# Out_current_sensor_UVW.net
KiCad netlist of a schematic drawn in Altium Designer
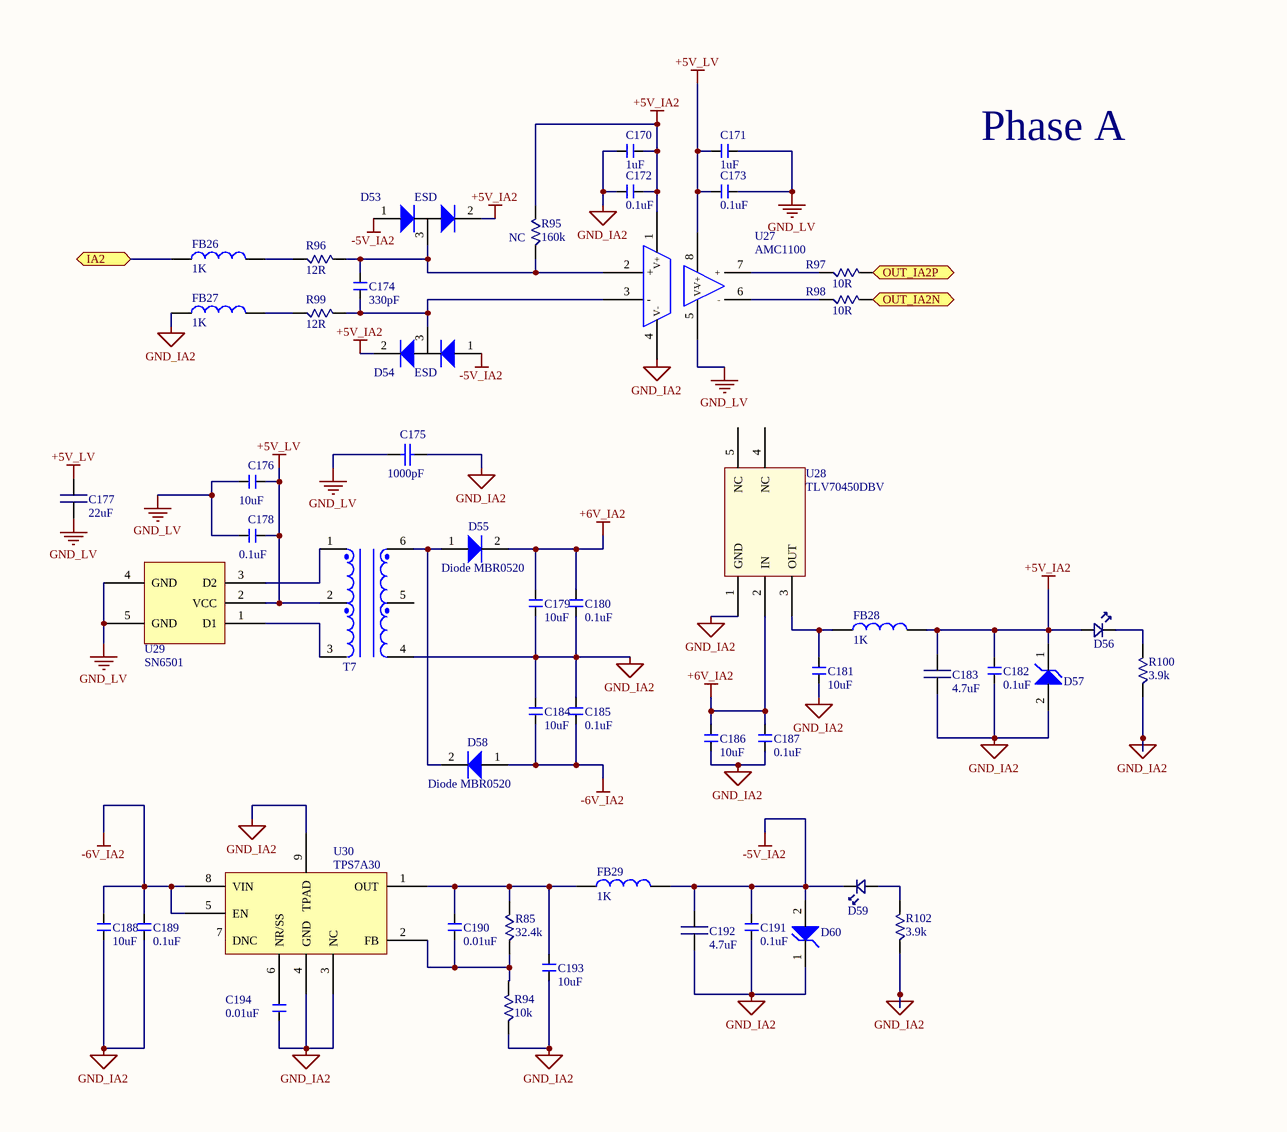
[diagram p0: Out_current_sensor_UVW.SchDoc, top left]
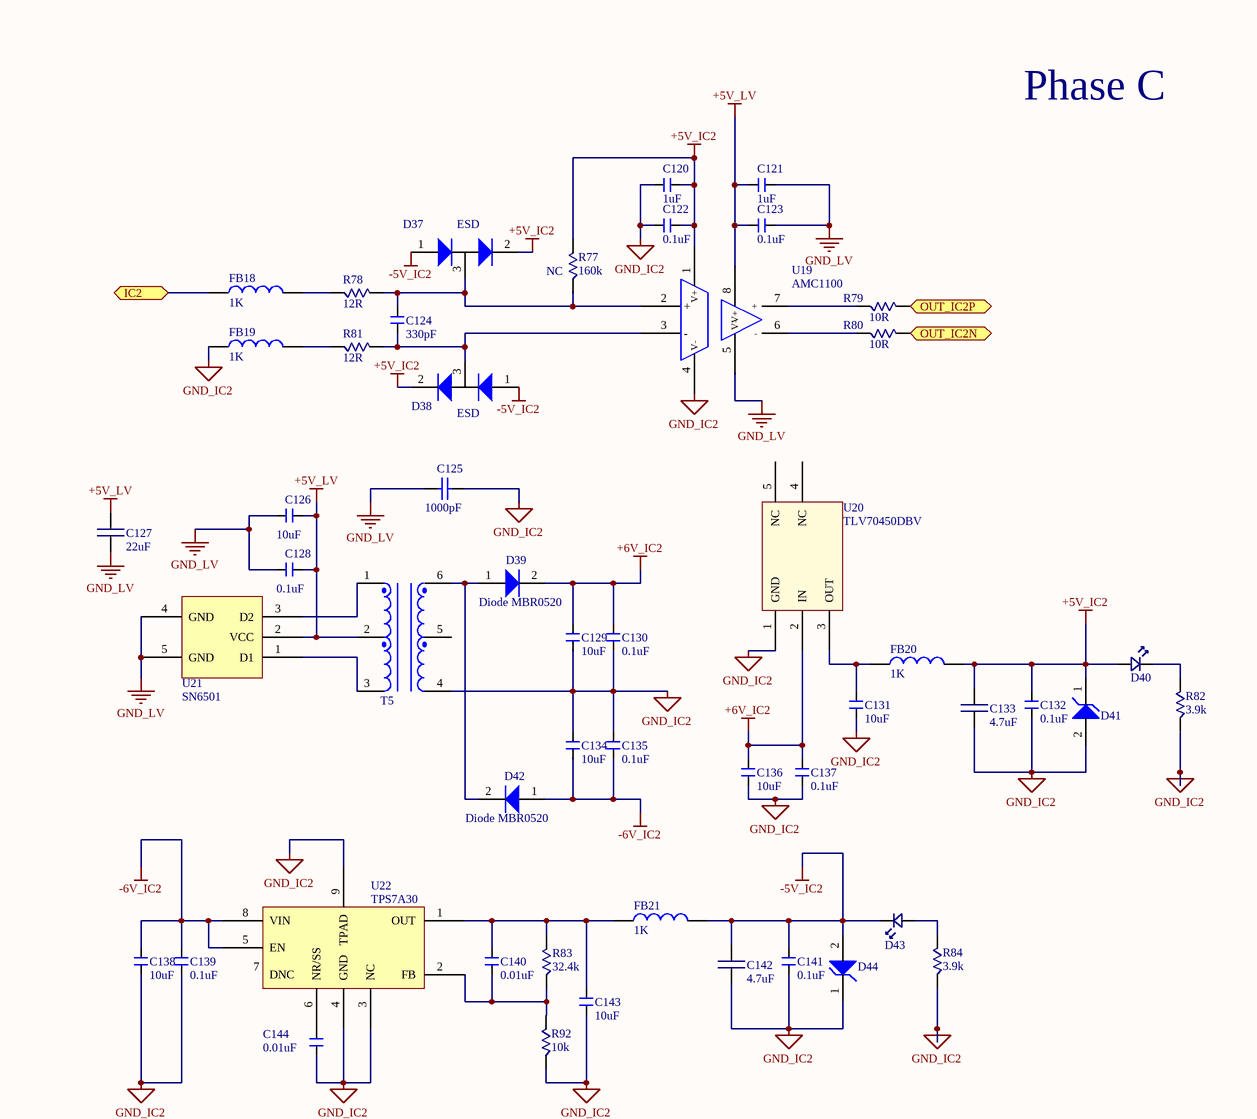
[diagram p1: Out_current_sensor_UVW.SchDoc, top right]
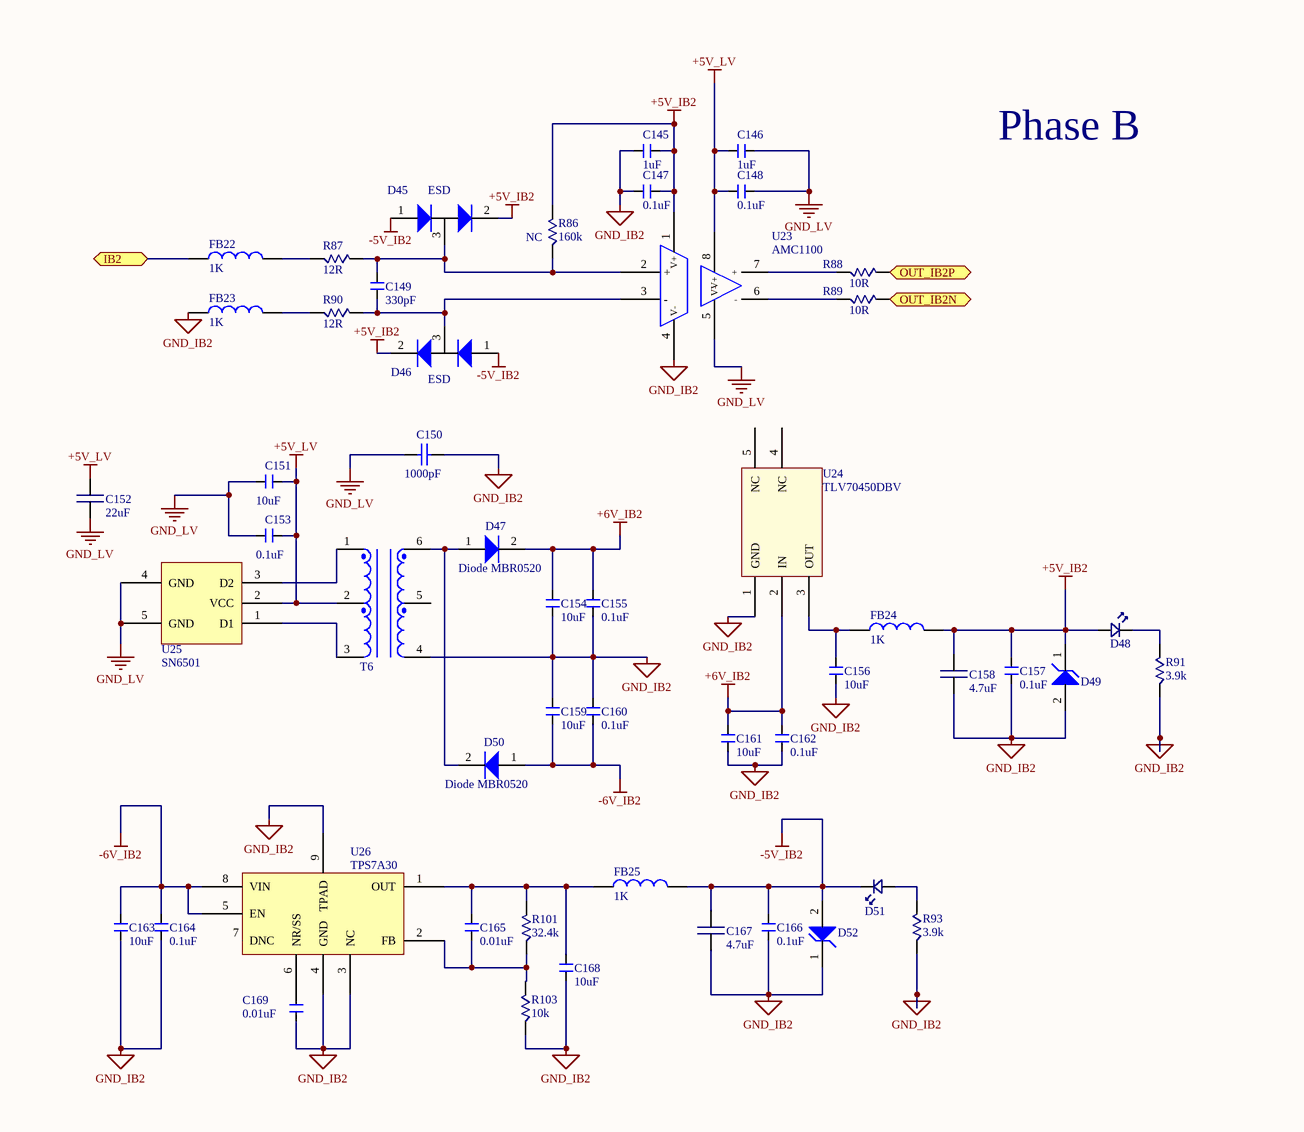
[diagram p2: Out_current_sensor_UVW.SchDoc, bottom left]

(export (version "E")
  (design (tool "Eeschema 10.0.6"))
  (components
    (comp (ref "C120")
      (value "1uF")
      (footprint "0603 (1608 Metric)")
      (description "CAP CER 1UF 50V X5R 0603")
      (fields (field (name "PART") "1276-1860-1-ND") (field (name "Comment") "Cap 0603_new"))
      (libsource (lib "Library_Microgrid") (part "Cap 0603_new"))
    )
    (comp (ref "C121")
      (value "1uF")
      (footprint "0603 (1608 Metric)")
      (description "CAP CER 1UF 50V X5R 0603")
      (fields (field (name "PART") "1276-1860-1-ND") (field (name "Comment") "Cap 0603_new"))
      (libsource (lib "Library_Microgrid") (part "Cap 0603_new"))
    )
    (comp (ref "C122")
      (value "0.1uF")
      (footprint "0603 (1608 Metric)")
      (description "CAP CER 0.1UF 50V Y5V 0603")
      (fields (field (name "PART") "311-1343-6-ND") (field (name "Comment") "Cap 0603_new"))
      (libsource (lib "Library_Microgrid") (part "Cap 0603_new"))
    )
    (comp (ref "C123")
      (value "0.1uF")
      (footprint "0603 (1608 Metric)")
      (description "CAP CER 0.1UF 50V Y5V 0603")
      (fields (field (name "PART") "311-1343-6-ND") (field (name "Comment") "Cap 0603_new"))
      (libsource (lib "Library_Microgrid") (part "Cap 0603_new"))
    )
    (comp (ref "C124")
      (value "330pF")
      (footprint "0603 (1608 Metric)")
      (description "CAP CER 330PF 50V C0G 0603")
      (fields (field (name "PART") "445-7033-2-ND") (field (name "Comment") "Cap 0603_new"))
      (libsource (lib "Library_Microgrid") (part "Cap 0603_new"))
    )
    (comp (ref "C125")
      (value "1000pF")
      (footprint "RAD-0.3")
      (description "CAP CER 1000PF 1KV Y5P RADIAL")
      (fields
        (field (name "PART") "1251PH-ND")
        (field (name "Comment") "Cap TH")
        (field (name "PUBLISHER") "Altium Limited")
      )
      (libsource (lib "Miscellaneous Devices") (part "Cap"))
    )
    (comp (ref "C126")
      (value "10uF")
      (footprint "0603 (1608 Metric)")
      (description "CAP CER 10UF 35V X5R 0805")
      (fields (field (name "PART") "490-10515-1-ND") (field (name "Comment") "Cap 0603_new"))
      (libsource (lib "Library_Microgrid") (part "Cap 0603_new"))
    )
    (comp (ref "C127")
      (value "22uF")
      (footprint "0805 (2012 metric)")
      (description "CAP CER 22UF 35V X5R 0805")
      (fields (field (name "PART") "445-14428-1-ND") (field (name "Comment") "Cap 0805"))
      (libsource (lib "Library_Microgrid") (part "Cap 0805"))
    )
    (comp (ref "C128")
      (value "0.1uF")
      (footprint "0603 (1608 Metric)")
      (description "CAP CER 0.1UF 50V Y5V 0603")
      (fields (field (name "PART") "311-1343-6-ND") (field (name "Comment") "Cap 0603_new"))
      (libsource (lib "Library_Microgrid") (part "Cap 0603_new"))
    )
    (comp (ref "C129")
      (value "10uF")
      (footprint "0603 (1608 Metric)")
      (description "CAP CER 10UF 35V X5R 0805")
      (fields (field (name "PART") "490-10515-1-ND") (field (name "Comment") "Cap 0603_new"))
      (libsource (lib "Library_Microgrid") (part "Cap 0603_new"))
    )
    (comp (ref "C130")
      (value "0.1uF")
      (footprint "0603 (1608 Metric)")
      (description "CAP CER 0.1UF 50V Y5V 0603")
      (fields (field (name "PART") "311-1343-6-ND") (field (name "Comment") "Cap 0603_new"))
      (libsource (lib "Library_Microgrid") (part "Cap 0603_new"))
    )
    (comp (ref "C131")
      (value "10uF")
      (footprint "0603 (1608 Metric)")
      (description "CAP CER 10UF 35V X5R 0805")
      (fields (field (name "PART") "490-10515-1-ND") (field (name "Comment") "Cap 0603_new"))
      (libsource (lib "Library_Microgrid") (part "Cap 0603_new"))
    )
    (comp (ref "C132")
      (value "0.1uF")
      (footprint "0603 (1608 Metric)")
      (description "CAP CER 0.1UF 50V Y5V 0603")
      (fields (field (name "PART") "311-1343-6-ND") (field (name "Comment") "Cap 0603_new"))
      (libsource (lib "Library_Microgrid") (part "Cap 0603_new"))
    )
    (comp (ref "C133")
      (value "4.7uF")
      (footprint "0805 (2012 metric)")
      (description "CAP CER 4.7UF 50V X5R 0805")
      (fields (field (name "PART") "445-5980-1-ND") (field (name "Comment") "Cap 0805"))
      (libsource (lib "Library_Microgrid") (part "Cap 0805"))
    )
    (comp (ref "C134")
      (value "10uF")
      (footprint "0603 (1608 Metric)")
      (description "CAP CER 10UF 35V X5R 0805")
      (fields (field (name "PART") "490-10515-1-ND") (field (name "Comment") "Cap 0603_new"))
      (libsource (lib "Library_Microgrid") (part "Cap 0603_new"))
    )
    (comp (ref "C135")
      (value "0.1uF")
      (footprint "0603 (1608 Metric)")
      (description "CAP CER 0.1UF 50V Y5V 0603")
      (fields (field (name "PART") "311-1343-6-ND") (field (name "Comment") "Cap 0603_new"))
      (libsource (lib "Library_Microgrid") (part "Cap 0603_new"))
    )
    (comp (ref "C136")
      (value "10uF")
      (footprint "0603 (1608 Metric)")
      (description "CAP CER 10UF 35V X5R 0805")
      (fields (field (name "PART") "490-10515-1-ND") (field (name "Comment") "Cap 0603_new"))
      (libsource (lib "Library_Microgrid") (part "Cap 0603_new"))
    )
    (comp (ref "C137")
      (value "0.1uF")
      (footprint "0603 (1608 Metric)")
      (description "CAP CER 0.1UF 50V Y5V 0603")
      (fields (field (name "PART") "311-1343-6-ND") (field (name "Comment") "Cap 0603_new"))
      (libsource (lib "Library_Microgrid") (part "Cap 0603_new"))
    )
    (comp (ref "C138")
      (value "10uF")
      (footprint "0603 (1608 Metric)")
      (description "CAP CER 10UF 35V X5R 0805")
      (fields (field (name "PART") "490-10515-1-ND") (field (name "Comment") "Cap 0603_new"))
      (libsource (lib "Library_Microgrid") (part "Cap 0603_new"))
    )
    (comp (ref "C139")
      (value "0.1uF")
      (footprint "0603 (1608 Metric)")
      (description "CAP CER 0.1UF 50V Y5V 0603")
      (fields (field (name "PART") "311-1343-6-ND") (field (name "Comment") "Cap 0603_new"))
      (libsource (lib "Library_Microgrid") (part "Cap 0603_new"))
    )
    (comp (ref "C140")
      (value "0.01uF")
      (footprint "0603 (1608 Metric)")
      (description "CAP CER 10000PF 100V X7R 0603")
      (fields (field (name "PART") "478-7418-1-ND") (field (name "Comment") "Cap 0603_new"))
      (libsource (lib "Library_Microgrid") (part "Cap 0603_new"))
    )
    (comp (ref "C141")
      (value "0.1uF")
      (footprint "0603 (1608 Metric)")
      (description "CAP CER 0.1UF 50V Y5V 0603")
      (fields (field (name "PART") "311-1343-6-ND") (field (name "Comment") "Cap 0603_new"))
      (libsource (lib "Library_Microgrid") (part "Cap 0603_new"))
    )
    (comp (ref "C142")
      (value "4.7uF")
      (footprint "0805 (2012 metric)")
      (description "CAP CER 4.7UF 50V X5R 0805")
      (fields (field (name "PART") "445-5980-1-ND") (field (name "Comment") "Cap 0805"))
      (libsource (lib "Library_Microgrid") (part "Cap 0805"))
    )
    (comp (ref "C143")
      (value "10uF")
      (footprint "0603 (1608 Metric)")
      (description "CAP CER 10UF 35V X5R 0805")
      (fields (field (name "PART") "490-10515-1-ND") (field (name "Comment") "Cap 0603_new"))
      (libsource (lib "Library_Microgrid") (part "Cap 0603_new"))
    )
    (comp (ref "C144")
      (value "0.01uF")
      (footprint "0603 (1608 Metric)")
      (description "CAP CER 10000PF 100V X7R 0603")
      (fields (field (name "PART") "478-7418-1-ND") (field (name "Comment") "Cap 0603_new"))
      (libsource (lib "Library_Microgrid") (part "Cap 0603_new"))
    )
    (comp (ref "C145")
      (value "1uF")
      (footprint "0603 (1608 Metric)")
      (description "CAP CER 1UF 50V X5R 0603")
      (fields (field (name "PART") "1276-1860-1-ND") (field (name "Comment") "Cap 0603_new"))
      (libsource (lib "Library_Microgrid") (part "Cap 0603_new"))
    )
    (comp (ref "C146")
      (value "1uF")
      (footprint "0603 (1608 Metric)")
      (description "CAP CER 1UF 50V X5R 0603")
      (fields (field (name "PART") "1276-1860-1-ND") (field (name "Comment") "Cap 0603_new"))
      (libsource (lib "Library_Microgrid") (part "Cap 0603_new"))
    )
    (comp (ref "C147")
      (value "0.1uF")
      (footprint "0603 (1608 Metric)")
      (description "CAP CER 0.1UF 50V Y5V 0603")
      (fields (field (name "PART") "311-1343-6-ND") (field (name "Comment") "Cap 0603_new"))
      (libsource (lib "Library_Microgrid") (part "Cap 0603_new"))
    )
    (comp (ref "C148")
      (value "0.1uF")
      (footprint "0603 (1608 Metric)")
      (description "CAP CER 0.1UF 50V Y5V 0603")
      (fields (field (name "PART") "311-1343-6-ND") (field (name "Comment") "Cap 0603_new"))
      (libsource (lib "Library_Microgrid") (part "Cap 0603_new"))
    )
    (comp (ref "C149")
      (value "330pF")
      (footprint "0603 (1608 Metric)")
      (description "CAP CER 330PF 50V C0G 0603")
      (fields (field (name "PART") "445-7033-2-ND") (field (name "Comment") "Cap 0603_new"))
      (libsource (lib "Library_Microgrid") (part "Cap 0603_new"))
    )
    (comp (ref "C150")
      (value "1000pF")
      (footprint "RAD-0.3")
      (description "CAP CER 1000PF 1KV Y5P RADIAL")
      (fields
        (field (name "PART") "1251PH-ND")
        (field (name "Comment") "Cap TH")
        (field (name "PUBLISHER") "Altium Limited")
      )
      (libsource (lib "Miscellaneous Devices") (part "Cap"))
    )
    (comp (ref "C151")
      (value "10uF")
      (footprint "0603 (1608 Metric)")
      (description "CAP CER 10UF 35V X5R 0805")
      (fields (field (name "PART") "490-10515-1-ND") (field (name "Comment") "Cap 0603_new"))
      (libsource (lib "Library_Microgrid") (part "Cap 0603_new"))
    )
    (comp (ref "C152")
      (value "22uF")
      (footprint "0805 (2012 metric)")
      (description "CAP CER 22UF 35V X5R 0805")
      (fields (field (name "PART") "445-14428-1-ND") (field (name "Comment") "Cap 0805"))
      (libsource (lib "Library_Microgrid") (part "Cap 0805"))
    )
    (comp (ref "C153")
      (value "0.1uF")
      (footprint "0603 (1608 Metric)")
      (description "CAP CER 0.1UF 50V Y5V 0603")
      (fields (field (name "PART") "311-1343-6-ND") (field (name "Comment") "Cap 0603_new"))
      (libsource (lib "Library_Microgrid") (part "Cap 0603_new"))
    )
    (comp (ref "C154")
      (value "10uF")
      (footprint "0603 (1608 Metric)")
      (description "CAP CER 10UF 35V X5R 0805")
      (fields (field (name "PART") "490-10515-1-ND") (field (name "Comment") "Cap 0603_new"))
      (libsource (lib "Library_Microgrid") (part "Cap 0603_new"))
    )
    (comp (ref "C155")
      (value "0.1uF")
      (footprint "0603 (1608 Metric)")
      (description "CAP CER 0.1UF 50V Y5V 0603")
      (fields (field (name "PART") "311-1343-6-ND") (field (name "Comment") "Cap 0603_new"))
      (libsource (lib "Library_Microgrid") (part "Cap 0603_new"))
    )
    (comp (ref "C156")
      (value "10uF")
      (footprint "0603 (1608 Metric)")
      (description "CAP CER 10UF 35V X5R 0805")
      (fields (field (name "PART") "490-10515-1-ND") (field (name "Comment") "Cap 0603_new"))
      (libsource (lib "Library_Microgrid") (part "Cap 0603_new"))
    )
    (comp (ref "C157")
      (value "0.1uF")
      (footprint "0603 (1608 Metric)")
      (description "CAP CER 0.1UF 50V Y5V 0603")
      (fields (field (name "PART") "311-1343-6-ND") (field (name "Comment") "Cap 0603_new"))
      (libsource (lib "Library_Microgrid") (part "Cap 0603_new"))
    )
    (comp (ref "C158")
      (value "4.7uF")
      (footprint "0805 (2012 metric)")
      (description "CAP CER 4.7UF 50V X5R 0805")
      (fields (field (name "PART") "445-5980-1-ND") (field (name "Comment") "Cap 0805"))
      (libsource (lib "Library_Microgrid") (part "Cap 0805"))
    )
    (comp (ref "C159")
      (value "10uF")
      (footprint "0603 (1608 Metric)")
      (description "CAP CER 10UF 35V X5R 0805")
      (fields (field (name "PART") "490-10515-1-ND") (field (name "Comment") "Cap 0603_new"))
      (libsource (lib "Library_Microgrid") (part "Cap 0603_new"))
    )
    (comp (ref "C160")
      (value "0.1uF")
      (footprint "0603 (1608 Metric)")
      (description "CAP CER 0.1UF 50V Y5V 0603")
      (fields (field (name "PART") "311-1343-6-ND") (field (name "Comment") "Cap 0603_new"))
      (libsource (lib "Library_Microgrid") (part "Cap 0603_new"))
    )
    (comp (ref "C161")
      (value "10uF")
      (footprint "0603 (1608 Metric)")
      (description "CAP CER 10UF 35V X5R 0805")
      (fields (field (name "PART") "490-10515-1-ND") (field (name "Comment") "Cap 0603_new"))
      (libsource (lib "Library_Microgrid") (part "Cap 0603_new"))
    )
    (comp (ref "C162")
      (value "0.1uF")
      (footprint "0603 (1608 Metric)")
      (description "CAP CER 0.1UF 50V Y5V 0603")
      (fields (field (name "PART") "311-1343-6-ND") (field (name "Comment") "Cap 0603_new"))
      (libsource (lib "Library_Microgrid") (part "Cap 0603_new"))
    )
    (comp (ref "C163")
      (value "10uF")
      (footprint "0603 (1608 Metric)")
      (description "CAP CER 10UF 35V X5R 0805")
      (fields (field (name "PART") "490-10515-1-ND") (field (name "Comment") "Cap 0603_new"))
      (libsource (lib "Library_Microgrid") (part "Cap 0603_new"))
    )
    (comp (ref "C164")
      (value "0.1uF")
      (footprint "0603 (1608 Metric)")
      (description "CAP CER 0.1UF 50V Y5V 0603")
      (fields (field (name "PART") "311-1343-6-ND") (field (name "Comment") "Cap 0603_new"))
      (libsource (lib "Library_Microgrid") (part "Cap 0603_new"))
    )
    (comp (ref "C165")
      (value "0.01uF")
      (footprint "0603 (1608 Metric)")
      (description "CAP CER 10000PF 100V X7R 0603")
      (fields (field (name "PART") "478-7418-1-ND") (field (name "Comment") "Cap 0603_new"))
      (libsource (lib "Library_Microgrid") (part "Cap 0603_new"))
    )
    (comp (ref "C166")
      (value "0.1uF")
      (footprint "0603 (1608 Metric)")
      (description "CAP CER 0.1UF 50V Y5V 0603")
      (fields (field (name "PART") "311-1343-6-ND") (field (name "Comment") "Cap 0603_new"))
      (libsource (lib "Library_Microgrid") (part "Cap 0603_new"))
    )
    (comp (ref "C167")
      (value "4.7uF")
      (footprint "0805 (2012 metric)")
      (description "CAP CER 4.7UF 50V X5R 0805")
      (fields (field (name "PART") "445-5980-1-ND") (field (name "Comment") "Cap 0805"))
      (libsource (lib "Library_Microgrid") (part "Cap 0805"))
    )
    (comp (ref "C168")
      (value "10uF")
      (footprint "0603 (1608 Metric)")
      (description "CAP CER 10UF 35V X5R 0805")
      (fields (field (name "PART") "490-10515-1-ND") (field (name "Comment") "Cap 0603_new"))
      (libsource (lib "Library_Microgrid") (part "Cap 0603_new"))
    )
    (comp (ref "C169")
      (value "0.01uF")
      (footprint "0603 (1608 Metric)")
      (description "CAP CER 10000PF 100V X7R 0603")
      (fields (field (name "PART") "478-7418-1-ND") (field (name "Comment") "Cap 0603_new"))
      (libsource (lib "Library_Microgrid") (part "Cap 0603_new"))
    )
    (comp (ref "C170")
      (value "1uF")
      (footprint "0603 (1608 Metric)")
      (description "CAP CER 1UF 50V X5R 0603")
      (fields (field (name "PART") "1276-1860-1-ND") (field (name "Comment") "Cap 0603_new"))
      (libsource (lib "Library_Microgrid") (part "Cap 0603_new"))
    )
    (comp (ref "C171")
      (value "1uF")
      (footprint "0603 (1608 Metric)")
      (description "CAP CER 1UF 50V X5R 0603")
      (fields (field (name "PART") "1276-1860-1-ND") (field (name "Comment") "Cap 0603_new"))
      (libsource (lib "Library_Microgrid") (part "Cap 0603_new"))
    )
    (comp (ref "C172")
      (value "0.1uF")
      (footprint "0603 (1608 Metric)")
      (description "CAP CER 0.1UF 50V Y5V 0603")
      (fields (field (name "PART") "311-1343-6-ND") (field (name "Comment") "Cap 0603_new"))
      (libsource (lib "Library_Microgrid") (part "Cap 0603_new"))
    )
    (comp (ref "C173")
      (value "0.1uF")
      (footprint "0603 (1608 Metric)")
      (description "CAP CER 0.1UF 50V Y5V 0603")
      (fields (field (name "PART") "311-1343-6-ND") (field (name "Comment") "Cap 0603_new"))
      (libsource (lib "Library_Microgrid") (part "Cap 0603_new"))
    )
    (comp (ref "C174")
      (value "330pF")
      (footprint "0603 (1608 Metric)")
      (description "CAP CER 330PF 50V C0G 0603")
      (fields (field (name "PART") "445-7033-2-ND") (field (name "Comment") "Cap 0603_new"))
      (libsource (lib "Library_Microgrid") (part "Cap 0603_new"))
    )
    (comp (ref "C175")
      (value "1000pF")
      (footprint "RAD-0.3")
      (description "CAP CER 1000PF 1KV Y5P RADIAL")
      (fields
        (field (name "PART") "1251PH-ND")
        (field (name "Comment") "Cap TH")
        (field (name "PUBLISHER") "Altium Limited")
      )
      (libsource (lib "Miscellaneous Devices") (part "Cap"))
    )
    (comp (ref "C176")
      (value "10uF")
      (footprint "0603 (1608 Metric)")
      (description "CAP CER 10UF 35V X5R 0805")
      (fields (field (name "PART") "490-10515-1-ND") (field (name "Comment") "Cap 0603_new"))
      (libsource (lib "Library_Microgrid") (part "Cap 0603_new"))
    )
    (comp (ref "C177")
      (value "22uF")
      (footprint "0805 (2012 metric)")
      (description "CAP CER 22UF 35V X5R 0805")
      (fields (field (name "PART") "445-14428-1-ND") (field (name "Comment") "Cap 0805"))
      (libsource (lib "Library_Microgrid") (part "Cap 0805"))
    )
    (comp (ref "C178")
      (value "0.1uF")
      (footprint "0603 (1608 Metric)")
      (description "CAP CER 0.1UF 50V Y5V 0603")
      (fields (field (name "PART") "311-1343-6-ND") (field (name "Comment") "Cap 0603_new"))
      (libsource (lib "Library_Microgrid") (part "Cap 0603_new"))
    )
    (comp (ref "C179")
      (value "10uF")
      (footprint "0603 (1608 Metric)")
      (description "CAP CER 10UF 35V X5R 0805")
      (fields (field (name "PART") "490-10515-1-ND") (field (name "Comment") "Cap 0603_new"))
      (libsource (lib "Library_Microgrid") (part "Cap 0603_new"))
    )
    (comp (ref "C180")
      (value "0.1uF")
      (footprint "0603 (1608 Metric)")
      (description "CAP CER 0.1UF 50V Y5V 0603")
      (fields (field (name "PART") "311-1343-6-ND") (field (name "Comment") "Cap 0603_new"))
      (libsource (lib "Library_Microgrid") (part "Cap 0603_new"))
    )
    (comp (ref "C181")
      (value "10uF")
      (footprint "0603 (1608 Metric)")
      (description "CAP CER 10UF 35V X5R 0805")
      (fields (field (name "PART") "490-10515-1-ND") (field (name "Comment") "Cap 0603_new"))
      (libsource (lib "Library_Microgrid") (part "Cap 0603_new"))
    )
    (comp (ref "C182")
      (value "0.1uF")
      (footprint "0603 (1608 Metric)")
      (description "CAP CER 0.1UF 50V Y5V 0603")
      (fields (field (name "PART") "311-1343-6-ND") (field (name "Comment") "Cap 0603_new"))
      (libsource (lib "Library_Microgrid") (part "Cap 0603_new"))
    )
    (comp (ref "C183")
      (value "4.7uF")
      (footprint "0805 (2012 metric)")
      (description "CAP CER 4.7UF 50V X5R 0805")
      (fields (field (name "PART") "445-5980-1-ND") (field (name "Comment") "Cap 0805"))
      (libsource (lib "Library_Microgrid") (part "Cap 0805"))
    )
    (comp (ref "C184")
      (value "10uF")
      (footprint "0603 (1608 Metric)")
      (description "CAP CER 10UF 35V X5R 0805")
      (fields (field (name "PART") "490-10515-1-ND") (field (name "Comment") "Cap 0603_new"))
      (libsource (lib "Library_Microgrid") (part "Cap 0603_new"))
    )
    (comp (ref "C185")
      (value "0.1uF")
      (footprint "0603 (1608 Metric)")
      (description "CAP CER 0.1UF 50V Y5V 0603")
      (fields (field (name "PART") "311-1343-6-ND") (field (name "Comment") "Cap 0603_new"))
      (libsource (lib "Library_Microgrid") (part "Cap 0603_new"))
    )
    (comp (ref "C186")
      (value "10uF")
      (footprint "0603 (1608 Metric)")
      (description "CAP CER 10UF 35V X5R 0805")
      (fields (field (name "PART") "490-10515-1-ND") (field (name "Comment") "Cap 0603_new"))
      (libsource (lib "Library_Microgrid") (part "Cap 0603_new"))
    )
    (comp (ref "C187")
      (value "0.1uF")
      (footprint "0603 (1608 Metric)")
      (description "CAP CER 0.1UF 50V Y5V 0603")
      (fields (field (name "PART") "311-1343-6-ND") (field (name "Comment") "Cap 0603_new"))
      (libsource (lib "Library_Microgrid") (part "Cap 0603_new"))
    )
    (comp (ref "C188")
      (value "10uF")
      (footprint "0603 (1608 Metric)")
      (description "CAP CER 10UF 35V X5R 0805")
      (fields (field (name "PART") "490-10515-1-ND") (field (name "Comment") "Cap 0603_new"))
      (libsource (lib "Library_Microgrid") (part "Cap 0603_new"))
    )
    (comp (ref "C189")
      (value "0.1uF")
      (footprint "0603 (1608 Metric)")
      (description "CAP CER 0.1UF 50V Y5V 0603")
      (fields (field (name "PART") "311-1343-6-ND") (field (name "Comment") "Cap 0603_new"))
      (libsource (lib "Library_Microgrid") (part "Cap 0603_new"))
    )
    (comp (ref "C190")
      (value "0.01uF")
      (footprint "0603 (1608 Metric)")
      (description "CAP CER 10000PF 100V X7R 0603")
      (fields (field (name "PART") "478-7418-1-ND") (field (name "Comment") "Cap 0603_new"))
      (libsource (lib "Library_Microgrid") (part "Cap 0603_new"))
    )
    (comp (ref "C191")
      (value "0.1uF")
      (footprint "0603 (1608 Metric)")
      (description "CAP CER 0.1UF 50V Y5V 0603")
      (fields (field (name "PART") "311-1343-6-ND") (field (name "Comment") "Cap 0603_new"))
      (libsource (lib "Library_Microgrid") (part "Cap 0603_new"))
    )
    (comp (ref "C192")
      (value "4.7uF")
      (footprint "0805 (2012 metric)")
      (description "CAP CER 4.7UF 50V X5R 0805")
      (fields (field (name "PART") "445-5980-1-ND") (field (name "Comment") "Cap 0805"))
      (libsource (lib "Library_Microgrid") (part "Cap 0805"))
    )
    (comp (ref "C193")
      (value "10uF")
      (footprint "0603 (1608 Metric)")
      (description "CAP CER 10UF 35V X5R 0805")
      (fields (field (name "PART") "490-10515-1-ND") (field (name "Comment") "Cap 0603_new"))
      (libsource (lib "Library_Microgrid") (part "Cap 0603_new"))
    )
    (comp (ref "C194")
      (value "0.01uF")
      (footprint "0603 (1608 Metric)")
      (description "CAP CER 10000PF 100V X7R 0603")
      (fields (field (name "PART") "478-7418-1-ND") (field (name "Comment") "Cap 0603_new"))
      (libsource (lib "Library_Microgrid") (part "Cap 0603_new"))
    )
    (comp (ref "D37")
      (value "ESD")
      (footprint "SOT323_ESD")
      (description "TVS DIODE")
      (fields (field (name "PART") "ESD1P0RFWH6327XTSA1CT") (field (name "Comment") "TVS - Diodes"))
      (libsource (lib "Library_Microgrid") (part "Diode_ESD"))
    )
    (comp (ref "D38")
      (value "ESD")
      (footprint "SOT323_ESD")
      (description "TVS DIODE")
      (fields (field (name "PART") "ESD1P0RFWH6327XTSA1CT") (field (name "Comment") "TVS - Diodes"))
      (libsource (lib "Library_Microgrid") (part "Diode_ESD"))
    )
    (comp (ref "D39")
      (value "Diode MBR0520")
      (footprint "SOD-123")
      (description "DIODE SCHOTTKY 20V 500MA SOD123")
      (fields (field (name "PART") "MBR0520LT1GOSCT-ND"))
      (libsource (lib "Library_Microgrid") (part "Diode MBR0520"))
    )
    (comp (ref "D40")
      (value "LED")
      (footprint "0805 (2012 Metric) Diode")
      (description "LED 0805")
      (libsource (lib "Library_Microgrid") (part "LED"))
    )
    (comp (ref "D41")
      (value "Diode Zener POWERDI123")
      (footprint "POWERDI")
      (description "DIODE ZENER POWERDI123")
      (fields (field (name "PART") "DFLZ6V2DICT-ND"))
      (libsource (lib "Library_Microgrid") (part "Diode Zener POWERDI123"))
    )
    (comp (ref "D42")
      (value "Diode MBR0520")
      (footprint "SOD-123")
      (description "DIODE SCHOTTKY 20V 500MA SOD123")
      (fields (field (name "PART") "MBR0520LT1GOSCT-ND"))
      (libsource (lib "Library_Microgrid") (part "Diode MBR0520"))
    )
    (comp (ref "D43")
      (value "LED")
      (footprint "0805 (2012 Metric) Diode")
      (description "LED 0805")
      (libsource (lib "Library_Microgrid") (part "LED"))
    )
    (comp (ref "D44")
      (value "Diode Zener POWERDI123")
      (footprint "POWERDI")
      (description "DIODE ZENER POWERDI123")
      (fields (field (name "PART") "DFLZ6V2DICT-ND"))
      (libsource (lib "Library_Microgrid") (part "Diode Zener POWERDI123"))
    )
    (comp (ref "D45")
      (value "ESD")
      (footprint "SOT323_ESD")
      (description "TVS DIODE")
      (fields (field (name "PART") "ESD1P0RFWH6327XTSA1CT") (field (name "Comment") "TVS - Diodes"))
      (libsource (lib "Library_Microgrid") (part "Diode_ESD"))
    )
    (comp (ref "D46")
      (value "ESD")
      (footprint "SOT323_ESD")
      (description "TVS DIODE")
      (fields (field (name "PART") "ESD1P0RFWH6327XTSA1CT") (field (name "Comment") "TVS - Diodes"))
      (libsource (lib "Library_Microgrid") (part "Diode_ESD"))
    )
    (comp (ref "D47")
      (value "Diode MBR0520")
      (footprint "SOD-123")
      (description "DIODE SCHOTTKY 20V 500MA SOD123")
      (fields (field (name "PART") "MBR0520LT1GOSCT-ND"))
      (libsource (lib "Library_Microgrid") (part "Diode MBR0520"))
    )
    (comp (ref "D48")
      (value "LED")
      (footprint "0805 (2012 Metric) Diode")
      (description "LED 0805")
      (libsource (lib "Library_Microgrid") (part "LED"))
    )
    (comp (ref "D49")
      (value "Diode Zener POWERDI123")
      (footprint "POWERDI")
      (description "DIODE ZENER POWERDI123")
      (fields (field (name "PART") "DFLZ6V2DICT-ND"))
      (libsource (lib "Library_Microgrid") (part "Diode Zener POWERDI123"))
    )
    (comp (ref "D50")
      (value "Diode MBR0520")
      (footprint "SOD-123")
      (description "DIODE SCHOTTKY 20V 500MA SOD123")
      (fields (field (name "PART") "MBR0520LT1GOSCT-ND"))
      (libsource (lib "Library_Microgrid") (part "Diode MBR0520"))
    )
    (comp (ref "D51")
      (value "LED")
      (footprint "0805 (2012 Metric) Diode")
      (description "LED 0805")
      (libsource (lib "Library_Microgrid") (part "LED"))
    )
    (comp (ref "D52")
      (value "Diode Zener POWERDI123")
      (footprint "POWERDI")
      (description "DIODE ZENER POWERDI123")
      (fields (field (name "PART") "DFLZ6V2DICT-ND"))
      (libsource (lib "Library_Microgrid") (part "Diode Zener POWERDI123"))
    )
    (comp (ref "D53")
      (value "ESD")
      (footprint "SOT323_ESD")
      (description "TVS DIODE")
      (fields (field (name "PART") "ESD1P0RFWH6327XTSA1CT") (field (name "Comment") "TVS - Diodes"))
      (libsource (lib "Library_Microgrid") (part "Diode_ESD"))
    )
    (comp (ref "D54")
      (value "ESD")
      (footprint "SOT323_ESD")
      (description "TVS DIODE")
      (fields (field (name "PART") "ESD1P0RFWH6327XTSA1CT") (field (name "Comment") "TVS - Diodes"))
      (libsource (lib "Library_Microgrid") (part "Diode_ESD"))
    )
    (comp (ref "D55")
      (value "Diode MBR0520")
      (footprint "SOD-123")
      (description "DIODE SCHOTTKY 20V 500MA SOD123")
      (fields (field (name "PART") "MBR0520LT1GOSCT-ND"))
      (libsource (lib "Library_Microgrid") (part "Diode MBR0520"))
    )
    (comp (ref "D56")
      (value "LED")
      (footprint "0805 (2012 Metric) Diode")
      (description "LED 0805")
      (libsource (lib "Library_Microgrid") (part "LED"))
    )
    (comp (ref "D57")
      (value "Diode Zener POWERDI123")
      (footprint "POWERDI")
      (description "DIODE ZENER POWERDI123")
      (fields (field (name "PART") "DFLZ6V2DICT-ND"))
      (libsource (lib "Library_Microgrid") (part "Diode Zener POWERDI123"))
    )
    (comp (ref "D58")
      (value "Diode MBR0520")
      (footprint "SOD-123")
      (description "DIODE SCHOTTKY 20V 500MA SOD123")
      (fields (field (name "PART") "MBR0520LT1GOSCT-ND"))
      (libsource (lib "Library_Microgrid") (part "Diode MBR0520"))
    )
    (comp (ref "D59")
      (value "LED")
      (footprint "0805 (2012 Metric) Diode")
      (description "LED 0805")
      (libsource (lib "Library_Microgrid") (part "LED"))
    )
    (comp (ref "D60")
      (value "Diode Zener POWERDI123")
      (footprint "POWERDI")
      (description "DIODE ZENER POWERDI123")
      (fields (field (name "PART") "DFLZ6V2DICT-ND"))
      (libsource (lib "Library_Microgrid") (part "Diode Zener POWERDI123"))
    )
    (comp (ref "FB18")
      (value "1K")
      (footprint "0603 (1608 Metric)")
      (description "FERRITE BEAD 1 KOHM 0603 1LN")
      (fields (field (name "PART") "445-8672-1-ND") (field (name "Comment") "Ferrite bead"))
      (libsource (lib "Library_Microgrid") (part "Ferrite bead"))
    )
    (comp (ref "FB19")
      (value "1K")
      (footprint "0603 (1608 Metric)")
      (description "FERRITE BEAD 1 KOHM 0603 1LN")
      (fields (field (name "PART") "445-8672-1-ND") (field (name "Comment") "Ferrite bead"))
      (libsource (lib "Library_Microgrid") (part "Ferrite bead"))
    )
    (comp (ref "FB20")
      (value "1K")
      (footprint "0603 (1608 Metric)")
      (description "FERRITE BEAD 1 KOHM 0603 1LN")
      (fields (field (name "PART") "445-8672-1-ND") (field (name "Comment") "Ferrite bead"))
      (libsource (lib "Library_Microgrid") (part "Ferrite bead"))
    )
    (comp (ref "FB21")
      (value "1K")
      (footprint "0603 (1608 Metric)")
      (description "FERRITE BEAD 1 KOHM 0603 1LN")
      (fields (field (name "PART") "445-8672-1-ND") (field (name "Comment") "Ferrite bead"))
      (libsource (lib "Library_Microgrid") (part "Ferrite bead"))
    )
    (comp (ref "FB22")
      (value "1K")
      (footprint "0603 (1608 Metric)")
      (description "FERRITE BEAD 1 KOHM 0603 1LN")
      (fields (field (name "PART") "445-8672-1-ND") (field (name "Comment") "Ferrite bead"))
      (libsource (lib "Library_Microgrid") (part "Ferrite bead"))
    )
    (comp (ref "FB23")
      (value "1K")
      (footprint "0603 (1608 Metric)")
      (description "FERRITE BEAD 1 KOHM 0603 1LN")
      (fields (field (name "PART") "445-8672-1-ND") (field (name "Comment") "Ferrite bead"))
      (libsource (lib "Library_Microgrid") (part "Ferrite bead"))
    )
    (comp (ref "FB24")
      (value "1K")
      (footprint "0603 (1608 Metric)")
      (description "FERRITE BEAD 1 KOHM 0603 1LN")
      (fields (field (name "PART") "445-8672-1-ND") (field (name "Comment") "Ferrite bead"))
      (libsource (lib "Library_Microgrid") (part "Ferrite bead"))
    )
    (comp (ref "FB25")
      (value "1K")
      (footprint "0603 (1608 Metric)")
      (description "FERRITE BEAD 1 KOHM 0603 1LN")
      (fields (field (name "PART") "445-8672-1-ND") (field (name "Comment") "Ferrite bead"))
      (libsource (lib "Library_Microgrid") (part "Ferrite bead"))
    )
    (comp (ref "FB26")
      (value "1K")
      (footprint "0603 (1608 Metric)")
      (description "FERRITE BEAD 1 KOHM 0603 1LN")
      (fields (field (name "PART") "445-8672-1-ND") (field (name "Comment") "Ferrite bead"))
      (libsource (lib "Library_Microgrid") (part "Ferrite bead"))
    )
    (comp (ref "FB27")
      (value "1K")
      (footprint "0603 (1608 Metric)")
      (description "FERRITE BEAD 1 KOHM 0603 1LN")
      (fields (field (name "PART") "445-8672-1-ND") (field (name "Comment") "Ferrite bead"))
      (libsource (lib "Library_Microgrid") (part "Ferrite bead"))
    )
    (comp (ref "FB28")
      (value "1K")
      (footprint "0603 (1608 Metric)")
      (description "FERRITE BEAD 1 KOHM 0603 1LN")
      (fields (field (name "PART") "445-8672-1-ND") (field (name "Comment") "Ferrite bead"))
      (libsource (lib "Library_Microgrid") (part "Ferrite bead"))
    )
    (comp (ref "FB29")
      (value "1K")
      (footprint "0603 (1608 Metric)")
      (description "FERRITE BEAD 1 KOHM 0603 1LN")
      (fields (field (name "PART") "445-8672-1-ND") (field (name "Comment") "Ferrite bead"))
      (libsource (lib "Library_Microgrid") (part "Ferrite bead"))
    )
    (comp (ref "R77")
      (value "NC")
      (footprint "0603 (1608 Metric)")
      (description "Resistor 0603")
      (fields (field (name "ALTIUM_VALUE") "160k"))
      (libsource (lib "Library_Microgrid") (part "Resistor 0603"))
    )
    (comp (ref "R78")
      (value "12R")
      (footprint "1206")
      (description "12 Ohm ±0.5% 0.25W, 1/4W Chip Resistor 1206")
      (fields (field (name "PART") "311-2961-1-ND") (field (name "Comment") "Resistor 1206"))
      (libsource (lib "Library_Microgrid") (part "Resistor 1206"))
    )
    (comp (ref "R79")
      (value "10R")
      (footprint "0603 (1608 Metric)")
      (description "RES SMD 10 OHM 0.05% 1/10W 0603")
      (fields (field (name "PART") "RNCF0603AKT10R0CT-ND") (field (name "Comment") "Resistor 0603"))
      (libsource (lib "Library_Microgrid") (part "Resistor 0603"))
    )
    (comp (ref "R80")
      (value "10R")
      (footprint "0603 (1608 Metric)")
      (description "RES SMD 10 OHM 0.05% 1/10W 0603")
      (fields (field (name "PART") "RNCF0603AKT10R0CT-ND") (field (name "Comment") "Resistor 0603"))
      (libsource (lib "Library_Microgrid") (part "Resistor 0603"))
    )
    (comp (ref "R81")
      (value "12R")
      (footprint "1206")
      (description "12 Ohm ±0.5% 0.25W, 1/4W Chip Resistor 1206")
      (fields (field (name "PART") "311-2961-1-ND") (field (name "Comment") "Resistor 1206"))
      (libsource (lib "Library_Microgrid") (part "Resistor 1206"))
    )
    (comp (ref "R82")
      (value "3.9k")
      (footprint "0603 (1608 Metric)")
      (description "RES SMD 3.9K OHM 5% 1/10W 0603")
      (fields (field (name "PART") "541-3.9KGCT-ND") (field (name "Comment") "Resistor 0603"))
      (libsource (lib "Library_Microgrid") (part "Resistor 0603"))
    )
    (comp (ref "R83")
      (value "32.4k")
      (footprint "0603 (1608 Metric)")
      (description "RES SMD 32.4KOHM 0.5% 1/10W 0603")
      (fields (field (name "PART") "311-32.4KDCT-ND") (field (name "Comment") "Resistor 0603"))
      (libsource (lib "Library_Microgrid") (part "Resistor 0603"))
    )
    (comp (ref "R84")
      (value "3.9k")
      (footprint "0603 (1608 Metric)")
      (description "RES SMD 3.9K OHM 5% 1/10W 0603")
      (fields (field (name "PART") "541-3.9KGCT-ND") (field (name "Comment") "Resistor 0603"))
      (libsource (lib "Library_Microgrid") (part "Resistor 0603"))
    )
    (comp (ref "R85")
      (value "32.4k")
      (footprint "0603 (1608 Metric)")
      (description "RES SMD 32.4KOHM 0.5% 1/10W 0603")
      (fields (field (name "PART") "311-32.4KDCT-ND") (field (name "Comment") "Resistor 0603"))
      (libsource (lib "Library_Microgrid") (part "Resistor 0603"))
    )
    (comp (ref "R86")
      (value "NC")
      (footprint "0603 (1608 Metric)")
      (description "Resistor 0603")
      (fields (field (name "ALTIUM_VALUE") "160k"))
      (libsource (lib "Library_Microgrid") (part "Resistor 0603"))
    )
    (comp (ref "R87")
      (value "12R")
      (footprint "1206")
      (description "12 Ohm ±0.5% 0.25W, 1/4W Chip Resistor 1206")
      (fields (field (name "PART") "311-2961-1-ND") (field (name "Comment") "Resistor 1206"))
      (libsource (lib "Library_Microgrid") (part "Resistor 1206"))
    )
    (comp (ref "R88")
      (value "10R")
      (footprint "0603 (1608 Metric)")
      (description "RES SMD 10 OHM 0.05% 1/10W 0603")
      (fields (field (name "PART") "RNCF0603AKT10R0CT-ND") (field (name "Comment") "Resistor 0603"))
      (libsource (lib "Library_Microgrid") (part "Resistor 0603"))
    )
    (comp (ref "R89")
      (value "10R")
      (footprint "0603 (1608 Metric)")
      (description "RES SMD 10 OHM 0.05% 1/10W 0603")
      (fields (field (name "PART") "RNCF0603AKT10R0CT-ND") (field (name "Comment") "Resistor 0603"))
      (libsource (lib "Library_Microgrid") (part "Resistor 0603"))
    )
    (comp (ref "R90")
      (value "12R")
      (footprint "1206")
      (description "12 Ohm ±0.5% 0.25W, 1/4W Chip Resistor 1206")
      (fields (field (name "PART") "311-2961-1-ND") (field (name "Comment") "Resistor 1206"))
      (libsource (lib "Library_Microgrid") (part "Resistor 1206"))
    )
    (comp (ref "R91")
      (value "3.9k")
      (footprint "0603 (1608 Metric)")
      (description "RES SMD 3.9K OHM 5% 1/10W 0603")
      (fields (field (name "PART") "541-3.9KGCT-ND") (field (name "Comment") "Resistor 0603"))
      (libsource (lib "Library_Microgrid") (part "Resistor 0603"))
    )
    (comp (ref "R92")
      (value "10k")
      (footprint "0603 (1608 Metric)")
      (description "RES SMD 10K OHM 0.5% 1/16W 0603")
      (fields (field (name "PART") "RR08P10.0KDCT-ND") (field (name "Comment") "Resistor 0603"))
      (libsource (lib "Library_Microgrid") (part "Resistor 0603"))
    )
    (comp (ref "R93")
      (value "3.9k")
      (footprint "0603 (1608 Metric)")
      (description "RES SMD 3.9K OHM 5% 1/10W 0603")
      (fields (field (name "PART") "541-3.9KGCT-ND") (field (name "Comment") "Resistor 0603"))
      (libsource (lib "Library_Microgrid") (part "Resistor 0603"))
    )
    (comp (ref "R94")
      (value "10k")
      (footprint "0603 (1608 Metric)")
      (description "RES SMD 10K OHM 0.5% 1/16W 0603")
      (fields (field (name "PART") "RR08P10.0KDCT-ND") (field (name "Comment") "Resistor 0603"))
      (libsource (lib "Library_Microgrid") (part "Resistor 0603"))
    )
    (comp (ref "R95")
      (value "NC")
      (footprint "0603 (1608 Metric)")
      (description "Resistor 0603")
      (fields (field (name "ALTIUM_VALUE") "160k"))
      (libsource (lib "Library_Microgrid") (part "Resistor 0603"))
    )
    (comp (ref "R96")
      (value "12R")
      (footprint "1206")
      (description "12 Ohm ±0.5% 0.25W, 1/4W Chip Resistor 1206")
      (fields (field (name "PART") "311-2961-1-ND") (field (name "Comment") "Resistor 1206"))
      (libsource (lib "Library_Microgrid") (part "Resistor 1206"))
    )
    (comp (ref "R97")
      (value "10R")
      (footprint "0603 (1608 Metric)")
      (description "RES SMD 10 OHM 0.05% 1/10W 0603")
      (fields (field (name "PART") "RNCF0603AKT10R0CT-ND") (field (name "Comment") "Resistor 0603"))
      (libsource (lib "Library_Microgrid") (part "Resistor 0603"))
    )
    (comp (ref "R98")
      (value "10R")
      (footprint "0603 (1608 Metric)")
      (description "RES SMD 10 OHM 0.05% 1/10W 0603")
      (fields (field (name "PART") "RNCF0603AKT10R0CT-ND") (field (name "Comment") "Resistor 0603"))
      (libsource (lib "Library_Microgrid") (part "Resistor 0603"))
    )
    (comp (ref "R99")
      (value "12R")
      (footprint "1206")
      (description "12 Ohm ±0.5% 0.25W, 1/4W Chip Resistor 1206")
      (fields (field (name "PART") "311-2961-1-ND") (field (name "Comment") "Resistor 1206"))
      (libsource (lib "Library_Microgrid") (part "Resistor 1206"))
    )
    (comp (ref "R100")
      (value "3.9k")
      (footprint "0603 (1608 Metric)")
      (description "RES SMD 3.9K OHM 5% 1/10W 0603")
      (fields (field (name "PART") "541-3.9KGCT-ND") (field (name "Comment") "Resistor 0603"))
      (libsource (lib "Library_Microgrid") (part "Resistor 0603"))
    )
    (comp (ref "R101")
      (value "32.4k")
      (footprint "0603 (1608 Metric)")
      (description "RES SMD 32.4KOHM 0.5% 1/10W 0603")
      (fields (field (name "PART") "311-32.4KDCT-ND") (field (name "Comment") "Resistor 0603"))
      (libsource (lib "Library_Microgrid") (part "Resistor 0603"))
    )
    (comp (ref "R102")
      (value "3.9k")
      (footprint "0603 (1608 Metric)")
      (description "RES SMD 3.9K OHM 5% 1/10W 0603")
      (fields (field (name "PART") "541-3.9KGCT-ND") (field (name "Comment") "Resistor 0603"))
      (libsource (lib "Library_Microgrid") (part "Resistor 0603"))
    )
    (comp (ref "R103")
      (value "10k")
      (footprint "0603 (1608 Metric)")
      (description "RES SMD 10K OHM 0.5% 1/16W 0603")
      (fields (field (name "PART") "RR08P10.0KDCT-ND") (field (name "Comment") "Resistor 0603"))
      (libsource (lib "Library_Microgrid") (part "Resistor 0603"))
    )
    (comp (ref "T5")
      (value "750313769")
      (footprint "Xmr SN6501")
      (description "TRANSFORMER SMD TR1.7 SN6501")
      (fields (field (name "PART") "1297-1107-1-ND"))
      (libsource (lib "Library_Microgrid") (part "750313769"))
    )
    (comp (ref "T6")
      (value "750313769")
      (footprint "Xmr SN6501")
      (description "TRANSFORMER SMD TR1.7 SN6501")
      (fields (field (name "PART") "1297-1107-1-ND"))
      (libsource (lib "Library_Microgrid") (part "750313769"))
    )
    (comp (ref "T7")
      (value "750313769")
      (footprint "Xmr SN6501")
      (description "TRANSFORMER SMD TR1.7 SN6501")
      (fields (field (name "PART") "1297-1107-1-ND"))
      (libsource (lib "Library_Microgrid") (part "750313769"))
    )
    (comp (ref "U19")
      (value "AMC1100")
      (footprint "SOIC8")
      (description "IC OPAMP ISOLATION 100KHZ 8SOIC")
      (fields (field (name "PART") "296-38822-5-ND"))
      (libsource (lib "Library_Microgrid") (part "AMC1100"))
    )
    (comp (ref "U20")
      (value "TLV70450DBV")
      (footprint "SOT23-5")
      (description "IC REG LDO 5V 0.15A SOT23-5")
      (fields (field (name "PART") "296-39287-1-ND"))
      (libsource (lib "Library_Microgrid") (part "TLV70450DBV"))
    )
    (comp (ref "U21")
      (value "SN6501")
      (footprint "SOT23-5")
      (description "IC REG CONV PWR SUPPLIES SOT23-5")
      (fields (field (name "PART") "296-37700-1-ND"))
      (libsource (lib "Library_Microgrid") (part "SN6501"))
    )
    (comp (ref "U22")
      (value "TPS7A30")
      (footprint "8-TSSOP")
      (description "IC REG LDO NEG ADJ 0.2A 8MSOP")
      (fields (field (name "PART") "296-27750-1-ND"))
      (libsource (lib "Library_Microgrid") (part "TPS7A30"))
    )
    (comp (ref "U23")
      (value "AMC1100")
      (footprint "SOIC8")
      (description "IC OPAMP ISOLATION 100KHZ 8SOIC")
      (fields (field (name "PART") "296-38822-5-ND"))
      (libsource (lib "Library_Microgrid") (part "AMC1100"))
    )
    (comp (ref "U24")
      (value "TLV70450DBV")
      (footprint "SOT23-5")
      (description "IC REG LDO 5V 0.15A SOT23-5")
      (fields (field (name "PART") "296-39287-1-ND"))
      (libsource (lib "Library_Microgrid") (part "TLV70450DBV"))
    )
    (comp (ref "U25")
      (value "SN6501")
      (footprint "SOT23-5")
      (description "IC REG CONV PWR SUPPLIES SOT23-5")
      (fields (field (name "PART") "296-37700-1-ND"))
      (libsource (lib "Library_Microgrid") (part "SN6501"))
    )
    (comp (ref "U26")
      (value "TPS7A30")
      (footprint "8-TSSOP")
      (description "IC REG LDO NEG ADJ 0.2A 8MSOP")
      (fields (field (name "PART") "296-27750-1-ND"))
      (libsource (lib "Library_Microgrid") (part "TPS7A30"))
    )
    (comp (ref "U27")
      (value "AMC1100")
      (footprint "SOIC8")
      (description "IC OPAMP ISOLATION 100KHZ 8SOIC")
      (fields (field (name "PART") "296-38822-5-ND"))
      (libsource (lib "Library_Microgrid") (part "AMC1100"))
    )
    (comp (ref "U28")
      (value "TLV70450DBV")
      (footprint "SOT23-5")
      (description "IC REG LDO 5V 0.15A SOT23-5")
      (fields (field (name "PART") "296-39287-1-ND"))
      (libsource (lib "Library_Microgrid") (part "TLV70450DBV"))
    )
    (comp (ref "U29")
      (value "SN6501")
      (footprint "SOT23-5")
      (description "IC REG CONV PWR SUPPLIES SOT23-5")
      (fields (field (name "PART") "296-37700-1-ND"))
      (libsource (lib "Library_Microgrid") (part "SN6501"))
    )
    (comp (ref "U30")
      (value "TPS7A30")
      (footprint "8-TSSOP")
      (description "IC REG LDO NEG ADJ 0.2A 8MSOP")
      (fields (field (name "PART") "296-27750-1-ND"))
      (libsource (lib "Library_Microgrid") (part "TPS7A30"))
    )
  )
  (nets
    (net (code "1") (name "+5V_IA2") (class "Default")
      (node (ref "C170") (pin "2") (pinfunction "OUT_2") (pintype "passive"))
      (node (ref "C172") (pin "2") (pinfunction "OUT_2") (pintype "passive"))
      (node (ref "C182") (pin "2") (pinfunction "OUT_2") (pintype "passive"))
      (node (ref "C183") (pin "2") (pinfunction "OUT_2") (pintype "passive"))
      (node (ref "D53") (pin "2") (pinfunction "node_2") (pintype "passive"))
      (node (ref "D54") (pin "2") (pinfunction "node_2") (pintype "passive"))
      (node (ref "D56") (pin "A") (pinfunction "A_A") (pintype "passive"))
      (node (ref "D57") (pin "1") (pinfunction "Anode_1") (pintype "passive"))
      (node (ref "FB28") (pin "2") (pinfunction "OUT_2") (pintype "passive"))
      (node (ref "R95") (pin "2") (pinfunction "A_2") (pintype "passive"))
      (node (ref "U27") (pin "1") (pinfunction "V+_1") (pintype "passive"))
    )
    (net (code "2") (name "+5V_IB2") (class "Default")
      (node (ref "C145") (pin "2") (pinfunction "OUT_2") (pintype "passive"))
      (node (ref "C147") (pin "2") (pinfunction "OUT_2") (pintype "passive"))
      (node (ref "C157") (pin "2") (pinfunction "OUT_2") (pintype "passive"))
      (node (ref "C158") (pin "2") (pinfunction "OUT_2") (pintype "passive"))
      (node (ref "D45") (pin "2") (pinfunction "node_2") (pintype "passive"))
      (node (ref "D46") (pin "2") (pinfunction "node_2") (pintype "passive"))
      (node (ref "D48") (pin "A") (pinfunction "A_A") (pintype "passive"))
      (node (ref "D49") (pin "1") (pinfunction "Anode_1") (pintype "passive"))
      (node (ref "FB24") (pin "2") (pinfunction "OUT_2") (pintype "passive"))
      (node (ref "R86") (pin "2") (pinfunction "A_2") (pintype "passive"))
      (node (ref "U23") (pin "1") (pinfunction "V+_1") (pintype "passive"))
    )
    (net (code "3") (name "+5V_IC2") (class "Default")
      (node (ref "C120") (pin "2") (pinfunction "OUT_2") (pintype "passive"))
      (node (ref "C122") (pin "2") (pinfunction "OUT_2") (pintype "passive"))
      (node (ref "C132") (pin "2") (pinfunction "OUT_2") (pintype "passive"))
      (node (ref "C133") (pin "2") (pinfunction "OUT_2") (pintype "passive"))
      (node (ref "D37") (pin "2") (pinfunction "node_2") (pintype "passive"))
      (node (ref "D38") (pin "2") (pinfunction "node_2") (pintype "passive"))
      (node (ref "D40") (pin "A") (pinfunction "A_A") (pintype "passive"))
      (node (ref "D41") (pin "1") (pinfunction "Anode_1") (pintype "passive"))
      (node (ref "FB20") (pin "2") (pinfunction "OUT_2") (pintype "passive"))
      (node (ref "R77") (pin "2") (pinfunction "A_2") (pintype "passive"))
      (node (ref "U19") (pin "1") (pinfunction "V+_1") (pintype "passive"))
    )
    (net (code "4") (name "+5V_LV") (class "Default")
      (node (ref "C121") (pin "1") (pinfunction "OUT_1") (pintype "passive"))
      (node (ref "C123") (pin "1") (pinfunction "OUT_1") (pintype "passive"))
      (node (ref "C126") (pin "2") (pinfunction "OUT_2") (pintype "passive"))
      (node (ref "C127") (pin "2") (pinfunction "OUT_2") (pintype "passive"))
      (node (ref "C128") (pin "2") (pinfunction "OUT_2") (pintype "passive"))
      (node (ref "C146") (pin "1") (pinfunction "OUT_1") (pintype "passive"))
      (node (ref "C148") (pin "1") (pinfunction "OUT_1") (pintype "passive"))
      (node (ref "C151") (pin "2") (pinfunction "OUT_2") (pintype "passive"))
      (node (ref "C152") (pin "2") (pinfunction "OUT_2") (pintype "passive"))
      (node (ref "C153") (pin "2") (pinfunction "OUT_2") (pintype "passive"))
      (node (ref "C171") (pin "1") (pinfunction "OUT_1") (pintype "passive"))
      (node (ref "C173") (pin "1") (pinfunction "OUT_1") (pintype "passive"))
      (node (ref "C176") (pin "2") (pinfunction "OUT_2") (pintype "passive"))
      (node (ref "C177") (pin "2") (pinfunction "OUT_2") (pintype "passive"))
      (node (ref "C178") (pin "2") (pinfunction "OUT_2") (pintype "passive"))
      (node (ref "T5") (pin "2") (pinfunction "1_2") (pintype "passive"))
      (node (ref "T6") (pin "2") (pinfunction "1_2") (pintype "passive"))
      (node (ref "T7") (pin "2") (pinfunction "1_2") (pintype "passive"))
      (node (ref "U19") (pin "8") (pinfunction "V+_8") (pintype "passive"))
      (node (ref "U21") (pin "2") (pinfunction "VCC_2") (pintype "passive"))
      (node (ref "U23") (pin "8") (pinfunction "V+_8") (pintype "passive"))
      (node (ref "U25") (pin "2") (pinfunction "VCC_2") (pintype "passive"))
      (node (ref "U27") (pin "8") (pinfunction "V+_8") (pintype "passive"))
      (node (ref "U29") (pin "2") (pinfunction "VCC_2") (pintype "passive"))
    )
    (net (code "5") (name "+6V_IA2") (class "Default")
      (node (ref "C179") (pin "2") (pinfunction "OUT_2") (pintype "passive"))
      (node (ref "C180") (pin "2") (pinfunction "OUT_2") (pintype "passive"))
      (node (ref "C186") (pin "2") (pinfunction "OUT_2") (pintype "passive"))
      (node (ref "C187") (pin "2") (pinfunction "OUT_2") (pintype "passive"))
      (node (ref "D55") (pin "2") (pinfunction "Anode_2") (pintype "passive"))
      (node (ref "U28") (pin "2") (pinfunction "IN_2") (pintype "passive"))
    )
    (net (code "6") (name "+6V_IB2") (class "Default")
      (node (ref "C154") (pin "2") (pinfunction "OUT_2") (pintype "passive"))
      (node (ref "C155") (pin "2") (pinfunction "OUT_2") (pintype "passive"))
      (node (ref "C161") (pin "2") (pinfunction "OUT_2") (pintype "passive"))
      (node (ref "C162") (pin "2") (pinfunction "OUT_2") (pintype "passive"))
      (node (ref "D47") (pin "2") (pinfunction "Anode_2") (pintype "passive"))
      (node (ref "U24") (pin "2") (pinfunction "IN_2") (pintype "passive"))
    )
    (net (code "7") (name "+6V_IC2") (class "Default")
      (node (ref "C129") (pin "2") (pinfunction "OUT_2") (pintype "passive"))
      (node (ref "C130") (pin "2") (pinfunction "OUT_2") (pintype "passive"))
      (node (ref "C136") (pin "2") (pinfunction "OUT_2") (pintype "passive"))
      (node (ref "C137") (pin "2") (pinfunction "OUT_2") (pintype "passive"))
      (node (ref "D39") (pin "2") (pinfunction "Anode_2") (pintype "passive"))
      (node (ref "U20") (pin "2") (pinfunction "IN_2") (pintype "passive"))
    )
    (net (code "8") (name "-5V_IA2") (class "Default")
      (node (ref "C191") (pin "2") (pinfunction "OUT_2") (pintype "passive"))
      (node (ref "C192") (pin "2") (pinfunction "OUT_2") (pintype "passive"))
      (node (ref "D53") (pin "1") (pinfunction "node_1") (pintype "passive"))
      (node (ref "D54") (pin "1") (pinfunction "node_1") (pintype "passive"))
      (node (ref "D59") (pin "K") (pinfunction "K_K") (pintype "passive"))
      (node (ref "D60") (pin "2") (pinfunction "Anode_2") (pintype "passive"))
      (node (ref "FB29") (pin "2") (pinfunction "OUT_2") (pintype "passive"))
    )
    (net (code "9") (name "-5V_IB2") (class "Default")
      (node (ref "C166") (pin "2") (pinfunction "OUT_2") (pintype "passive"))
      (node (ref "C167") (pin "2") (pinfunction "OUT_2") (pintype "passive"))
      (node (ref "D45") (pin "1") (pinfunction "node_1") (pintype "passive"))
      (node (ref "D46") (pin "1") (pinfunction "node_1") (pintype "passive"))
      (node (ref "D51") (pin "K") (pinfunction "K_K") (pintype "passive"))
      (node (ref "D52") (pin "2") (pinfunction "Anode_2") (pintype "passive"))
      (node (ref "FB25") (pin "2") (pinfunction "OUT_2") (pintype "passive"))
    )
    (net (code "10") (name "-5V_IC2") (class "Default")
      (node (ref "C141") (pin "2") (pinfunction "OUT_2") (pintype "passive"))
      (node (ref "C142") (pin "2") (pinfunction "OUT_2") (pintype "passive"))
      (node (ref "D37") (pin "1") (pinfunction "node_1") (pintype "passive"))
      (node (ref "D38") (pin "1") (pinfunction "node_1") (pintype "passive"))
      (node (ref "D43") (pin "K") (pinfunction "K_K") (pintype "passive"))
      (node (ref "D44") (pin "2") (pinfunction "Anode_2") (pintype "passive"))
      (node (ref "FB21") (pin "2") (pinfunction "OUT_2") (pintype "passive"))
    )
    (net (code "11") (name "-6V_IA2") (class "Default")
      (node (ref "C184") (pin "1") (pinfunction "OUT_1") (pintype "passive"))
      (node (ref "C185") (pin "1") (pinfunction "OUT_1") (pintype "passive"))
      (node (ref "C188") (pin "2") (pinfunction "OUT_2") (pintype "passive"))
      (node (ref "C189") (pin "2") (pinfunction "OUT_2") (pintype "passive"))
      (node (ref "D58") (pin "1") (pinfunction "Anode_1") (pintype "passive"))
      (node (ref "U30") (pin "5") (pinfunction "EN_5") (pintype "passive"))
      (node (ref "U30") (pin "8") (pinfunction "VIN_8") (pintype "power_in"))
    )
    (net (code "12") (name "-6V_IB2") (class "Default")
      (node (ref "C159") (pin "1") (pinfunction "OUT_1") (pintype "passive"))
      (node (ref "C160") (pin "1") (pinfunction "OUT_1") (pintype "passive"))
      (node (ref "C163") (pin "2") (pinfunction "OUT_2") (pintype "passive"))
      (node (ref "C164") (pin "2") (pinfunction "OUT_2") (pintype "passive"))
      (node (ref "D50") (pin "1") (pinfunction "Anode_1") (pintype "passive"))
      (node (ref "U26") (pin "5") (pinfunction "EN_5") (pintype "passive"))
      (node (ref "U26") (pin "8") (pinfunction "VIN_8") (pintype "power_in"))
    )
    (net (code "13") (name "-6V_IC2") (class "Default")
      (node (ref "C134") (pin "1") (pinfunction "OUT_1") (pintype "passive"))
      (node (ref "C135") (pin "1") (pinfunction "OUT_1") (pintype "passive"))
      (node (ref "C138") (pin "2") (pinfunction "OUT_2") (pintype "passive"))
      (node (ref "C139") (pin "2") (pinfunction "OUT_2") (pintype "passive"))
      (node (ref "D42") (pin "1") (pinfunction "Anode_1") (pintype "passive"))
      (node (ref "U22") (pin "5") (pinfunction "EN_5") (pintype "passive"))
      (node (ref "U22") (pin "8") (pinfunction "VIN_8") (pintype "power_in"))
    )
    (net (code "14") (name "/IA2") (class "Default")
      (node (ref "FB26") (pin "1") (pinfunction "OUT_1") (pintype "passive"))
    )
    (net (code "15") (name "/IB2") (class "Default")
      (node (ref "FB22") (pin "1") (pinfunction "OUT_1") (pintype "passive"))
    )
    (net (code "16") (name "/IC2") (class "Default")
      (node (ref "FB18") (pin "1") (pinfunction "OUT_1") (pintype "passive"))
    )
    (net (code "17") (name "/OUT_IA2N") (class "Default")
      (node (ref "R98") (pin "2") (pinfunction "A_2") (pintype "passive"))
    )
    (net (code "18") (name "/OUT_IA2P") (class "Default")
      (node (ref "R97") (pin "2") (pinfunction "A_2") (pintype "passive"))
    )
    (net (code "19") (name "/OUT_IB2N") (class "Default")
      (node (ref "R89") (pin "2") (pinfunction "A_2") (pintype "passive"))
    )
    (net (code "20") (name "/OUT_IB2P") (class "Default")
      (node (ref "R88") (pin "2") (pinfunction "A_2") (pintype "passive"))
    )
    (net (code "21") (name "/OUT_IC2N") (class "Default")
      (node (ref "R80") (pin "2") (pinfunction "A_2") (pintype "passive"))
    )
    (net (code "22") (name "/OUT_IC2P") (class "Default")
      (node (ref "R79") (pin "2") (pinfunction "A_2") (pintype "passive"))
    )
    (net (code "23") (name "GND_IA2") (class "Default")
      (node (ref "C170") (pin "1") (pinfunction "OUT_1") (pintype "passive"))
      (node (ref "C172") (pin "1") (pinfunction "OUT_1") (pintype "passive"))
      (node (ref "C175") (pin "2") (pinfunction "2_2") (pintype "passive"))
      (node (ref "C179") (pin "1") (pinfunction "OUT_1") (pintype "passive"))
      (node (ref "C180") (pin "1") (pinfunction "OUT_1") (pintype "passive"))
      (node (ref "C181") (pin "1") (pinfunction "OUT_1") (pintype "passive"))
      (node (ref "C182") (pin "1") (pinfunction "OUT_1") (pintype "passive"))
      (node (ref "C183") (pin "1") (pinfunction "OUT_1") (pintype "passive"))
      (node (ref "C184") (pin "2") (pinfunction "OUT_2") (pintype "passive"))
      (node (ref "C185") (pin "2") (pinfunction "OUT_2") (pintype "passive"))
      (node (ref "C186") (pin "1") (pinfunction "OUT_1") (pintype "passive"))
      (node (ref "C187") (pin "1") (pinfunction "OUT_1") (pintype "passive"))
      (node (ref "C188") (pin "1") (pinfunction "OUT_1") (pintype "passive"))
      (node (ref "C189") (pin "1") (pinfunction "OUT_1") (pintype "passive"))
      (node (ref "C191") (pin "1") (pinfunction "OUT_1") (pintype "passive"))
      (node (ref "C192") (pin "1") (pinfunction "OUT_1") (pintype "passive"))
      (node (ref "C193") (pin "1") (pinfunction "OUT_1") (pintype "passive"))
      (node (ref "C194") (pin "1") (pinfunction "OUT_1") (pintype "passive"))
      (node (ref "D57") (pin "2") (pinfunction "Anode_2") (pintype "passive"))
      (node (ref "D60") (pin "1") (pinfunction "Anode_1") (pintype "passive"))
      (node (ref "FB27") (pin "1") (pinfunction "OUT_1") (pintype "passive"))
      (node (ref "R100") (pin "1") (pinfunction "A_1") (pintype "passive"))
      (node (ref "R102") (pin "1") (pinfunction "A_1") (pintype "passive"))
      (node (ref "R94") (pin "1") (pinfunction "A_1") (pintype "passive"))
      (node (ref "T7") (pin "4") (pinfunction "1_4") (pintype "passive"))
      (node (ref "U27") (pin "4") (pinfunction "V-_4") (pintype "passive"))
      (node (ref "U28") (pin "1") (pinfunction "GND_1") (pintype "passive"))
      (node (ref "U30") (pin "3") (pinfunction "NC_3") (pintype "passive"))
      (node (ref "U30") (pin "4") (pinfunction "GND_4") (pintype "power_in"))
      (node (ref "U30") (pin "9") (pinfunction "TPAD_9") (pintype "power_in"))
    )
    (net (code "24") (name "GND_IB2") (class "Default")
      (node (ref "C145") (pin "1") (pinfunction "OUT_1") (pintype "passive"))
      (node (ref "C147") (pin "1") (pinfunction "OUT_1") (pintype "passive"))
      (node (ref "C150") (pin "2") (pinfunction "2_2") (pintype "passive"))
      (node (ref "C154") (pin "1") (pinfunction "OUT_1") (pintype "passive"))
      (node (ref "C155") (pin "1") (pinfunction "OUT_1") (pintype "passive"))
      (node (ref "C156") (pin "1") (pinfunction "OUT_1") (pintype "passive"))
      (node (ref "C157") (pin "1") (pinfunction "OUT_1") (pintype "passive"))
      (node (ref "C158") (pin "1") (pinfunction "OUT_1") (pintype "passive"))
      (node (ref "C159") (pin "2") (pinfunction "OUT_2") (pintype "passive"))
      (node (ref "C160") (pin "2") (pinfunction "OUT_2") (pintype "passive"))
      (node (ref "C161") (pin "1") (pinfunction "OUT_1") (pintype "passive"))
      (node (ref "C162") (pin "1") (pinfunction "OUT_1") (pintype "passive"))
      (node (ref "C163") (pin "1") (pinfunction "OUT_1") (pintype "passive"))
      (node (ref "C164") (pin "1") (pinfunction "OUT_1") (pintype "passive"))
      (node (ref "C166") (pin "1") (pinfunction "OUT_1") (pintype "passive"))
      (node (ref "C167") (pin "1") (pinfunction "OUT_1") (pintype "passive"))
      (node (ref "C168") (pin "1") (pinfunction "OUT_1") (pintype "passive"))
      (node (ref "C169") (pin "1") (pinfunction "OUT_1") (pintype "passive"))
      (node (ref "D49") (pin "2") (pinfunction "Anode_2") (pintype "passive"))
      (node (ref "D52") (pin "1") (pinfunction "Anode_1") (pintype "passive"))
      (node (ref "FB23") (pin "1") (pinfunction "OUT_1") (pintype "passive"))
      (node (ref "R103") (pin "1") (pinfunction "A_1") (pintype "passive"))
      (node (ref "R91") (pin "1") (pinfunction "A_1") (pintype "passive"))
      (node (ref "R93") (pin "1") (pinfunction "A_1") (pintype "passive"))
      (node (ref "T6") (pin "4") (pinfunction "1_4") (pintype "passive"))
      (node (ref "U23") (pin "4") (pinfunction "V-_4") (pintype "passive"))
      (node (ref "U24") (pin "1") (pinfunction "GND_1") (pintype "passive"))
      (node (ref "U26") (pin "3") (pinfunction "NC_3") (pintype "passive"))
      (node (ref "U26") (pin "4") (pinfunction "GND_4") (pintype "power_in"))
      (node (ref "U26") (pin "9") (pinfunction "TPAD_9") (pintype "power_in"))
    )
    (net (code "25") (name "GND_IC2") (class "Default")
      (node (ref "C120") (pin "1") (pinfunction "OUT_1") (pintype "passive"))
      (node (ref "C122") (pin "1") (pinfunction "OUT_1") (pintype "passive"))
      (node (ref "C125") (pin "2") (pinfunction "2_2") (pintype "passive"))
      (node (ref "C129") (pin "1") (pinfunction "OUT_1") (pintype "passive"))
      (node (ref "C130") (pin "1") (pinfunction "OUT_1") (pintype "passive"))
      (node (ref "C131") (pin "1") (pinfunction "OUT_1") (pintype "passive"))
      (node (ref "C132") (pin "1") (pinfunction "OUT_1") (pintype "passive"))
      (node (ref "C133") (pin "1") (pinfunction "OUT_1") (pintype "passive"))
      (node (ref "C134") (pin "2") (pinfunction "OUT_2") (pintype "passive"))
      (node (ref "C135") (pin "2") (pinfunction "OUT_2") (pintype "passive"))
      (node (ref "C136") (pin "1") (pinfunction "OUT_1") (pintype "passive"))
      (node (ref "C137") (pin "1") (pinfunction "OUT_1") (pintype "passive"))
      (node (ref "C138") (pin "1") (pinfunction "OUT_1") (pintype "passive"))
      (node (ref "C139") (pin "1") (pinfunction "OUT_1") (pintype "passive"))
      (node (ref "C141") (pin "1") (pinfunction "OUT_1") (pintype "passive"))
      (node (ref "C142") (pin "1") (pinfunction "OUT_1") (pintype "passive"))
      (node (ref "C143") (pin "1") (pinfunction "OUT_1") (pintype "passive"))
      (node (ref "C144") (pin "1") (pinfunction "OUT_1") (pintype "passive"))
      (node (ref "D41") (pin "2") (pinfunction "Anode_2") (pintype "passive"))
      (node (ref "D44") (pin "1") (pinfunction "Anode_1") (pintype "passive"))
      (node (ref "FB19") (pin "1") (pinfunction "OUT_1") (pintype "passive"))
      (node (ref "R82") (pin "1") (pinfunction "A_1") (pintype "passive"))
      (node (ref "R84") (pin "1") (pinfunction "A_1") (pintype "passive"))
      (node (ref "R92") (pin "1") (pinfunction "A_1") (pintype "passive"))
      (node (ref "T5") (pin "4") (pinfunction "1_4") (pintype "passive"))
      (node (ref "U19") (pin "4") (pinfunction "V-_4") (pintype "passive"))
      (node (ref "U20") (pin "1") (pinfunction "GND_1") (pintype "passive"))
      (node (ref "U22") (pin "3") (pinfunction "NC_3") (pintype "passive"))
      (node (ref "U22") (pin "4") (pinfunction "GND_4") (pintype "power_in"))
      (node (ref "U22") (pin "9") (pinfunction "TPAD_9") (pintype "power_in"))
    )
    (net (code "26") (name "GND_LV") (class "Default")
      (node (ref "C121") (pin "2") (pinfunction "OUT_2") (pintype "passive"))
      (node (ref "C123") (pin "2") (pinfunction "OUT_2") (pintype "passive"))
      (node (ref "C125") (pin "1") (pinfunction "1_1") (pintype "passive"))
      (node (ref "C126") (pin "1") (pinfunction "OUT_1") (pintype "passive"))
      (node (ref "C127") (pin "1") (pinfunction "OUT_1") (pintype "passive"))
      (node (ref "C128") (pin "1") (pinfunction "OUT_1") (pintype "passive"))
      (node (ref "C146") (pin "2") (pinfunction "OUT_2") (pintype "passive"))
      (node (ref "C148") (pin "2") (pinfunction "OUT_2") (pintype "passive"))
      (node (ref "C150") (pin "1") (pinfunction "1_1") (pintype "passive"))
      (node (ref "C151") (pin "1") (pinfunction "OUT_1") (pintype "passive"))
      (node (ref "C152") (pin "1") (pinfunction "OUT_1") (pintype "passive"))
      (node (ref "C153") (pin "1") (pinfunction "OUT_1") (pintype "passive"))
      (node (ref "C171") (pin "2") (pinfunction "OUT_2") (pintype "passive"))
      (node (ref "C173") (pin "2") (pinfunction "OUT_2") (pintype "passive"))
      (node (ref "C175") (pin "1") (pinfunction "1_1") (pintype "passive"))
      (node (ref "C176") (pin "1") (pinfunction "OUT_1") (pintype "passive"))
      (node (ref "C177") (pin "1") (pinfunction "OUT_1") (pintype "passive"))
      (node (ref "C178") (pin "1") (pinfunction "OUT_1") (pintype "passive"))
      (node (ref "U19") (pin "5") (pinfunction "V-_5") (pintype "passive"))
      (node (ref "U21") (pin "4") (pinfunction "GND_4") (pintype "passive"))
      (node (ref "U21") (pin "5") (pinfunction "GND_5") (pintype "passive"))
      (node (ref "U23") (pin "5") (pinfunction "V-_5") (pintype "passive"))
      (node (ref "U25") (pin "4") (pinfunction "GND_4") (pintype "passive"))
      (node (ref "U25") (pin "5") (pinfunction "GND_5") (pintype "passive"))
      (node (ref "U27") (pin "5") (pinfunction "V-_5") (pintype "passive"))
      (node (ref "U29") (pin "4") (pinfunction "GND_4") (pintype "passive"))
      (node (ref "U29") (pin "5") (pinfunction "GND_5") (pintype "passive"))
    )
    (net (code "27") (name "Net-(C124-OUT-Pad1)") (class "Default")
      (node (ref "C124") (pin "1") (pinfunction "OUT_1") (pintype "passive"))
      (node (ref "D37") (pin "3") (pinfunction "node_3") (pintype "passive"))
      (node (ref "R77") (pin "1") (pinfunction "A_1") (pintype "passive"))
      (node (ref "R78") (pin "2") (pinfunction "A_2") (pintype "passive"))
      (node (ref "U19") (pin "2") (pinfunction "+_2") (pintype "passive"))
    )
    (net (code "28") (name "Net-(C124-OUT-Pad2)") (class "Default")
      (node (ref "C124") (pin "2") (pinfunction "OUT_2") (pintype "passive"))
      (node (ref "D38") (pin "3") (pinfunction "node_3") (pintype "passive"))
      (node (ref "R81") (pin "2") (pinfunction "A_2") (pintype "passive"))
      (node (ref "U19") (pin "3") (pinfunction "-_3") (pintype "passive"))
    )
    (net (code "29") (name "Net-(C149-OUT-Pad1)") (class "Default")
      (node (ref "C149") (pin "1") (pinfunction "OUT_1") (pintype "passive"))
      (node (ref "D45") (pin "3") (pinfunction "node_3") (pintype "passive"))
      (node (ref "R86") (pin "1") (pinfunction "A_1") (pintype "passive"))
      (node (ref "R87") (pin "2") (pinfunction "A_2") (pintype "passive"))
      (node (ref "U23") (pin "2") (pinfunction "+_2") (pintype "passive"))
    )
    (net (code "30") (name "Net-(C149-OUT-Pad2)") (class "Default")
      (node (ref "C149") (pin "2") (pinfunction "OUT_2") (pintype "passive"))
      (node (ref "D46") (pin "3") (pinfunction "node_3") (pintype "passive"))
      (node (ref "R90") (pin "2") (pinfunction "A_2") (pintype "passive"))
      (node (ref "U23") (pin "3") (pinfunction "-_3") (pintype "passive"))
    )
    (net (code "31") (name "Net-(C174-OUT-Pad1)") (class "Default")
      (node (ref "C174") (pin "1") (pinfunction "OUT_1") (pintype "passive"))
      (node (ref "D53") (pin "3") (pinfunction "node_3") (pintype "passive"))
      (node (ref "R95") (pin "1") (pinfunction "A_1") (pintype "passive"))
      (node (ref "R96") (pin "2") (pinfunction "A_2") (pintype "passive"))
      (node (ref "U27") (pin "2") (pinfunction "+_2") (pintype "passive"))
    )
    (net (code "32") (name "Net-(C174-OUT-Pad2)") (class "Default")
      (node (ref "C174") (pin "2") (pinfunction "OUT_2") (pintype "passive"))
      (node (ref "D54") (pin "3") (pinfunction "node_3") (pintype "passive"))
      (node (ref "R99") (pin "2") (pinfunction "A_2") (pintype "passive"))
      (node (ref "U27") (pin "3") (pinfunction "-_3") (pintype "passive"))
    )
    (net (code "33") (name "Net-(D39-Anode-Pad1)") (class "Default")
      (node (ref "D39") (pin "1") (pinfunction "Anode_1") (pintype "passive"))
      (node (ref "D42") (pin "2") (pinfunction "Anode_2") (pintype "passive"))
      (node (ref "T5") (pin "6") (pinfunction "1_6") (pintype "passive"))
    )
    (net (code "34") (name "Net-(D40-PadK)") (class "Default")
      (node (ref "D40") (pin "K") (pinfunction "K_K") (pintype "passive"))
      (node (ref "R82") (pin "2") (pinfunction "A_2") (pintype "passive"))
    )
    (net (code "35") (name "Net-(D43-PadA)") (class "Default")
      (node (ref "D43") (pin "A") (pinfunction "A_A") (pintype "passive"))
      (node (ref "R84") (pin "2") (pinfunction "A_2") (pintype "passive"))
    )
    (net (code "36") (name "Net-(D47-Anode-Pad1)") (class "Default")
      (node (ref "D47") (pin "1") (pinfunction "Anode_1") (pintype "passive"))
      (node (ref "D50") (pin "2") (pinfunction "Anode_2") (pintype "passive"))
      (node (ref "T6") (pin "6") (pinfunction "1_6") (pintype "passive"))
    )
    (net (code "37") (name "Net-(D48-PadK)") (class "Default")
      (node (ref "D48") (pin "K") (pinfunction "K_K") (pintype "passive"))
      (node (ref "R91") (pin "2") (pinfunction "A_2") (pintype "passive"))
    )
    (net (code "38") (name "Net-(D51-PadA)") (class "Default")
      (node (ref "D51") (pin "A") (pinfunction "A_A") (pintype "passive"))
      (node (ref "R93") (pin "2") (pinfunction "A_2") (pintype "passive"))
    )
    (net (code "39") (name "Net-(D55-Anode-Pad1)") (class "Default")
      (node (ref "D55") (pin "1") (pinfunction "Anode_1") (pintype "passive"))
      (node (ref "D58") (pin "2") (pinfunction "Anode_2") (pintype "passive"))
      (node (ref "T7") (pin "6") (pinfunction "1_6") (pintype "passive"))
    )
    (net (code "40") (name "Net-(D56-PadK)") (class "Default")
      (node (ref "D56") (pin "K") (pinfunction "K_K") (pintype "passive"))
      (node (ref "R100") (pin "2") (pinfunction "A_2") (pintype "passive"))
    )
    (net (code "41") (name "Net-(D59-PadA)") (class "Default")
      (node (ref "D59") (pin "A") (pinfunction "A_A") (pintype "passive"))
      (node (ref "R102") (pin "2") (pinfunction "A_2") (pintype "passive"))
    )
    (net (code "42") (name "Net-(FB18-OUT-Pad2)") (class "Default")
      (node (ref "FB18") (pin "2") (pinfunction "OUT_2") (pintype "passive"))
      (node (ref "R78") (pin "1") (pinfunction "A_1") (pintype "passive"))
    )
    (net (code "43") (name "Net-(FB19-OUT-Pad2)") (class "Default")
      (node (ref "FB19") (pin "2") (pinfunction "OUT_2") (pintype "passive"))
      (node (ref "R81") (pin "1") (pinfunction "A_1") (pintype "passive"))
    )
    (net (code "44") (name "Net-(FB22-OUT-Pad2)") (class "Default")
      (node (ref "FB22") (pin "2") (pinfunction "OUT_2") (pintype "passive"))
      (node (ref "R87") (pin "1") (pinfunction "A_1") (pintype "passive"))
    )
    (net (code "45") (name "Net-(FB23-OUT-Pad2)") (class "Default")
      (node (ref "FB23") (pin "2") (pinfunction "OUT_2") (pintype "passive"))
      (node (ref "R90") (pin "1") (pinfunction "A_1") (pintype "passive"))
    )
    (net (code "46") (name "Net-(FB26-OUT-Pad2)") (class "Default")
      (node (ref "FB26") (pin "2") (pinfunction "OUT_2") (pintype "passive"))
      (node (ref "R96") (pin "1") (pinfunction "A_1") (pintype "passive"))
    )
    (net (code "47") (name "Net-(FB27-OUT-Pad2)") (class "Default")
      (node (ref "FB27") (pin "2") (pinfunction "OUT_2") (pintype "passive"))
      (node (ref "R99") (pin "1") (pinfunction "A_1") (pintype "passive"))
    )
    (net (code "48") (name "Net-(R79-A-Pad1)") (class "Default")
      (node (ref "R79") (pin "1") (pinfunction "A_1") (pintype "passive"))
      (node (ref "U19") (pin "7") (pinfunction "+_7") (pintype "passive"))
    )
    (net (code "49") (name "Net-(R80-A-Pad1)") (class "Default")
      (node (ref "R80") (pin "1") (pinfunction "A_1") (pintype "passive"))
      (node (ref "U19") (pin "6") (pinfunction "-_6") (pintype "passive"))
    )
    (net (code "50") (name "Net-(R88-A-Pad1)") (class "Default")
      (node (ref "R88") (pin "1") (pinfunction "A_1") (pintype "passive"))
      (node (ref "U23") (pin "7") (pinfunction "+_7") (pintype "passive"))
    )
    (net (code "51") (name "Net-(R89-A-Pad1)") (class "Default")
      (node (ref "R89") (pin "1") (pinfunction "A_1") (pintype "passive"))
      (node (ref "U23") (pin "6") (pinfunction "-_6") (pintype "passive"))
    )
    (net (code "52") (name "Net-(R97-A-Pad1)") (class "Default")
      (node (ref "R97") (pin "1") (pinfunction "A_1") (pintype "passive"))
      (node (ref "U27") (pin "7") (pinfunction "+_7") (pintype "passive"))
    )
    (net (code "53") (name "Net-(R98-A-Pad1)") (class "Default")
      (node (ref "R98") (pin "1") (pinfunction "A_1") (pintype "passive"))
      (node (ref "U27") (pin "6") (pinfunction "-_6") (pintype "passive"))
    )
    (net (code "54") (name "Net-(U20-OUT)") (class "Default")
      (node (ref "C131") (pin "2") (pinfunction "OUT_2") (pintype "passive"))
      (node (ref "FB20") (pin "1") (pinfunction "OUT_1") (pintype "passive"))
      (node (ref "U20") (pin "3") (pinfunction "OUT_3") (pintype "passive"))
    )
    (net (code "55") (name "Net-(U21-D1)") (class "Default")
      (node (ref "T5") (pin "3") (pinfunction "1_3") (pintype "passive"))
      (node (ref "U21") (pin "1") (pinfunction "D1_1") (pintype "passive"))
    )
    (net (code "56") (name "Net-(U21-D2)") (class "Default")
      (node (ref "T5") (pin "1") (pinfunction "1_1") (pintype "passive"))
      (node (ref "U21") (pin "3") (pinfunction "D2_3") (pintype "passive"))
    )
    (net (code "57") (name "Net-(U22-FB)") (class "Default")
      (node (ref "C140") (pin "2") (pinfunction "OUT_2") (pintype "passive"))
      (node (ref "R83") (pin "1") (pinfunction "A_1") (pintype "passive"))
      (node (ref "R92") (pin "2") (pinfunction "A_2") (pintype "passive"))
      (node (ref "U22") (pin "2") (pinfunction "FB_2") (pintype "passive"))
    )
    (net (code "58") (name "Net-(U22-NR{slash}SS)") (class "Default")
      (node (ref "C144") (pin "2") (pinfunction "OUT_2") (pintype "passive"))
      (node (ref "U22") (pin "6") (pinfunction "NR/SS_6") (pintype "power_in"))
    )
    (net (code "59") (name "Net-(U22-OUT)") (class "Default")
      (node (ref "C140") (pin "1") (pinfunction "OUT_1") (pintype "passive"))
      (node (ref "C143") (pin "2") (pinfunction "OUT_2") (pintype "passive"))
      (node (ref "FB21") (pin "1") (pinfunction "OUT_1") (pintype "passive"))
      (node (ref "R83") (pin "2") (pinfunction "A_2") (pintype "passive"))
      (node (ref "U22") (pin "1") (pinfunction "OUT_1") (pintype "passive"))
    )
    (net (code "60") (name "Net-(U24-OUT)") (class "Default")
      (node (ref "C156") (pin "2") (pinfunction "OUT_2") (pintype "passive"))
      (node (ref "FB24") (pin "1") (pinfunction "OUT_1") (pintype "passive"))
      (node (ref "U24") (pin "3") (pinfunction "OUT_3") (pintype "passive"))
    )
    (net (code "61") (name "Net-(U25-D1)") (class "Default")
      (node (ref "T6") (pin "3") (pinfunction "1_3") (pintype "passive"))
      (node (ref "U25") (pin "1") (pinfunction "D1_1") (pintype "passive"))
    )
    (net (code "62") (name "Net-(U25-D2)") (class "Default")
      (node (ref "T6") (pin "1") (pinfunction "1_1") (pintype "passive"))
      (node (ref "U25") (pin "3") (pinfunction "D2_3") (pintype "passive"))
    )
    (net (code "63") (name "Net-(U26-FB)") (class "Default")
      (node (ref "C165") (pin "2") (pinfunction "OUT_2") (pintype "passive"))
      (node (ref "R101") (pin "1") (pinfunction "A_1") (pintype "passive"))
      (node (ref "R103") (pin "2") (pinfunction "A_2") (pintype "passive"))
      (node (ref "U26") (pin "2") (pinfunction "FB_2") (pintype "passive"))
    )
    (net (code "64") (name "Net-(U26-NR{slash}SS)") (class "Default")
      (node (ref "C169") (pin "2") (pinfunction "OUT_2") (pintype "passive"))
      (node (ref "U26") (pin "6") (pinfunction "NR/SS_6") (pintype "power_in"))
    )
    (net (code "65") (name "Net-(U26-OUT)") (class "Default")
      (node (ref "C165") (pin "1") (pinfunction "OUT_1") (pintype "passive"))
      (node (ref "C168") (pin "2") (pinfunction "OUT_2") (pintype "passive"))
      (node (ref "FB25") (pin "1") (pinfunction "OUT_1") (pintype "passive"))
      (node (ref "R101") (pin "2") (pinfunction "A_2") (pintype "passive"))
      (node (ref "U26") (pin "1") (pinfunction "OUT_1") (pintype "passive"))
    )
    (net (code "66") (name "Net-(U28-OUT)") (class "Default")
      (node (ref "C181") (pin "2") (pinfunction "OUT_2") (pintype "passive"))
      (node (ref "FB28") (pin "1") (pinfunction "OUT_1") (pintype "passive"))
      (node (ref "U28") (pin "3") (pinfunction "OUT_3") (pintype "passive"))
    )
    (net (code "67") (name "Net-(U29-D1)") (class "Default")
      (node (ref "T7") (pin "3") (pinfunction "1_3") (pintype "passive"))
      (node (ref "U29") (pin "1") (pinfunction "D1_1") (pintype "passive"))
    )
    (net (code "68") (name "Net-(U29-D2)") (class "Default")
      (node (ref "T7") (pin "1") (pinfunction "1_1") (pintype "passive"))
      (node (ref "U29") (pin "3") (pinfunction "D2_3") (pintype "passive"))
    )
    (net (code "69") (name "Net-(U30-FB)") (class "Default")
      (node (ref "C190") (pin "2") (pinfunction "OUT_2") (pintype "passive"))
      (node (ref "R85") (pin "1") (pinfunction "A_1") (pintype "passive"))
      (node (ref "R94") (pin "2") (pinfunction "A_2") (pintype "passive"))
      (node (ref "U30") (pin "2") (pinfunction "FB_2") (pintype "passive"))
    )
    (net (code "70") (name "Net-(U30-NR{slash}SS)") (class "Default")
      (node (ref "C194") (pin "2") (pinfunction "OUT_2") (pintype "passive"))
      (node (ref "U30") (pin "6") (pinfunction "NR/SS_6") (pintype "power_in"))
    )
    (net (code "71") (name "Net-(U30-OUT)") (class "Default")
      (node (ref "C190") (pin "1") (pinfunction "OUT_1") (pintype "passive"))
      (node (ref "C193") (pin "2") (pinfunction "OUT_2") (pintype "passive"))
      (node (ref "FB29") (pin "1") (pinfunction "OUT_1") (pintype "passive"))
      (node (ref "R85") (pin "2") (pinfunction "A_2") (pintype "passive"))
      (node (ref "U30") (pin "1") (pinfunction "OUT_1") (pintype "passive"))
    )
    (net (code "72") (name "unconnected-(T5-1-Pad5)") (class "Default")
      (node (ref "T5") (pin "5") (pinfunction "1_5") (pintype "passive"))
    )
    (net (code "73") (name "unconnected-(T6-1-Pad5)") (class "Default")
      (node (ref "T6") (pin "5") (pinfunction "1_5") (pintype "passive"))
    )
    (net (code "74") (name "unconnected-(T7-1-Pad5)") (class "Default")
      (node (ref "T7") (pin "5") (pinfunction "1_5") (pintype "passive"))
    )
    (net (code "75") (name "unconnected-(U20-NC-Pad4)") (class "Default")
      (node (ref "U20") (pin "4") (pinfunction "NC_4") (pintype "passive"))
    )
    (net (code "76") (name "unconnected-(U20-NC-Pad5)") (class "Default")
      (node (ref "U20") (pin "5") (pinfunction "NC_5") (pintype "passive"))
    )
    (net (code "77") (name "unconnected-(U22-DNC-Pad7)") (class "Default")
      (node (ref "U22") (pin "7") (pinfunction "DNC_7") (pintype "passive"))
    )
    (net (code "78") (name "unconnected-(U24-NC-Pad4)") (class "Default")
      (node (ref "U24") (pin "4") (pinfunction "NC_4") (pintype "passive"))
    )
    (net (code "79") (name "unconnected-(U24-NC-Pad5)") (class "Default")
      (node (ref "U24") (pin "5") (pinfunction "NC_5") (pintype "passive"))
    )
    (net (code "80") (name "unconnected-(U26-DNC-Pad7)") (class "Default")
      (node (ref "U26") (pin "7") (pinfunction "DNC_7") (pintype "passive"))
    )
    (net (code "81") (name "unconnected-(U28-NC-Pad4)") (class "Default")
      (node (ref "U28") (pin "4") (pinfunction "NC_4") (pintype "passive"))
    )
    (net (code "82") (name "unconnected-(U28-NC-Pad5)") (class "Default")
      (node (ref "U28") (pin "5") (pinfunction "NC_5") (pintype "passive"))
    )
    (net (code "83") (name "unconnected-(U30-DNC-Pad7)") (class "Default")
      (node (ref "U30") (pin "7") (pinfunction "DNC_7") (pintype "passive"))
    )
  )
)
